# light_controller.net
KiCad netlist of a schematic drawn in EAGLE
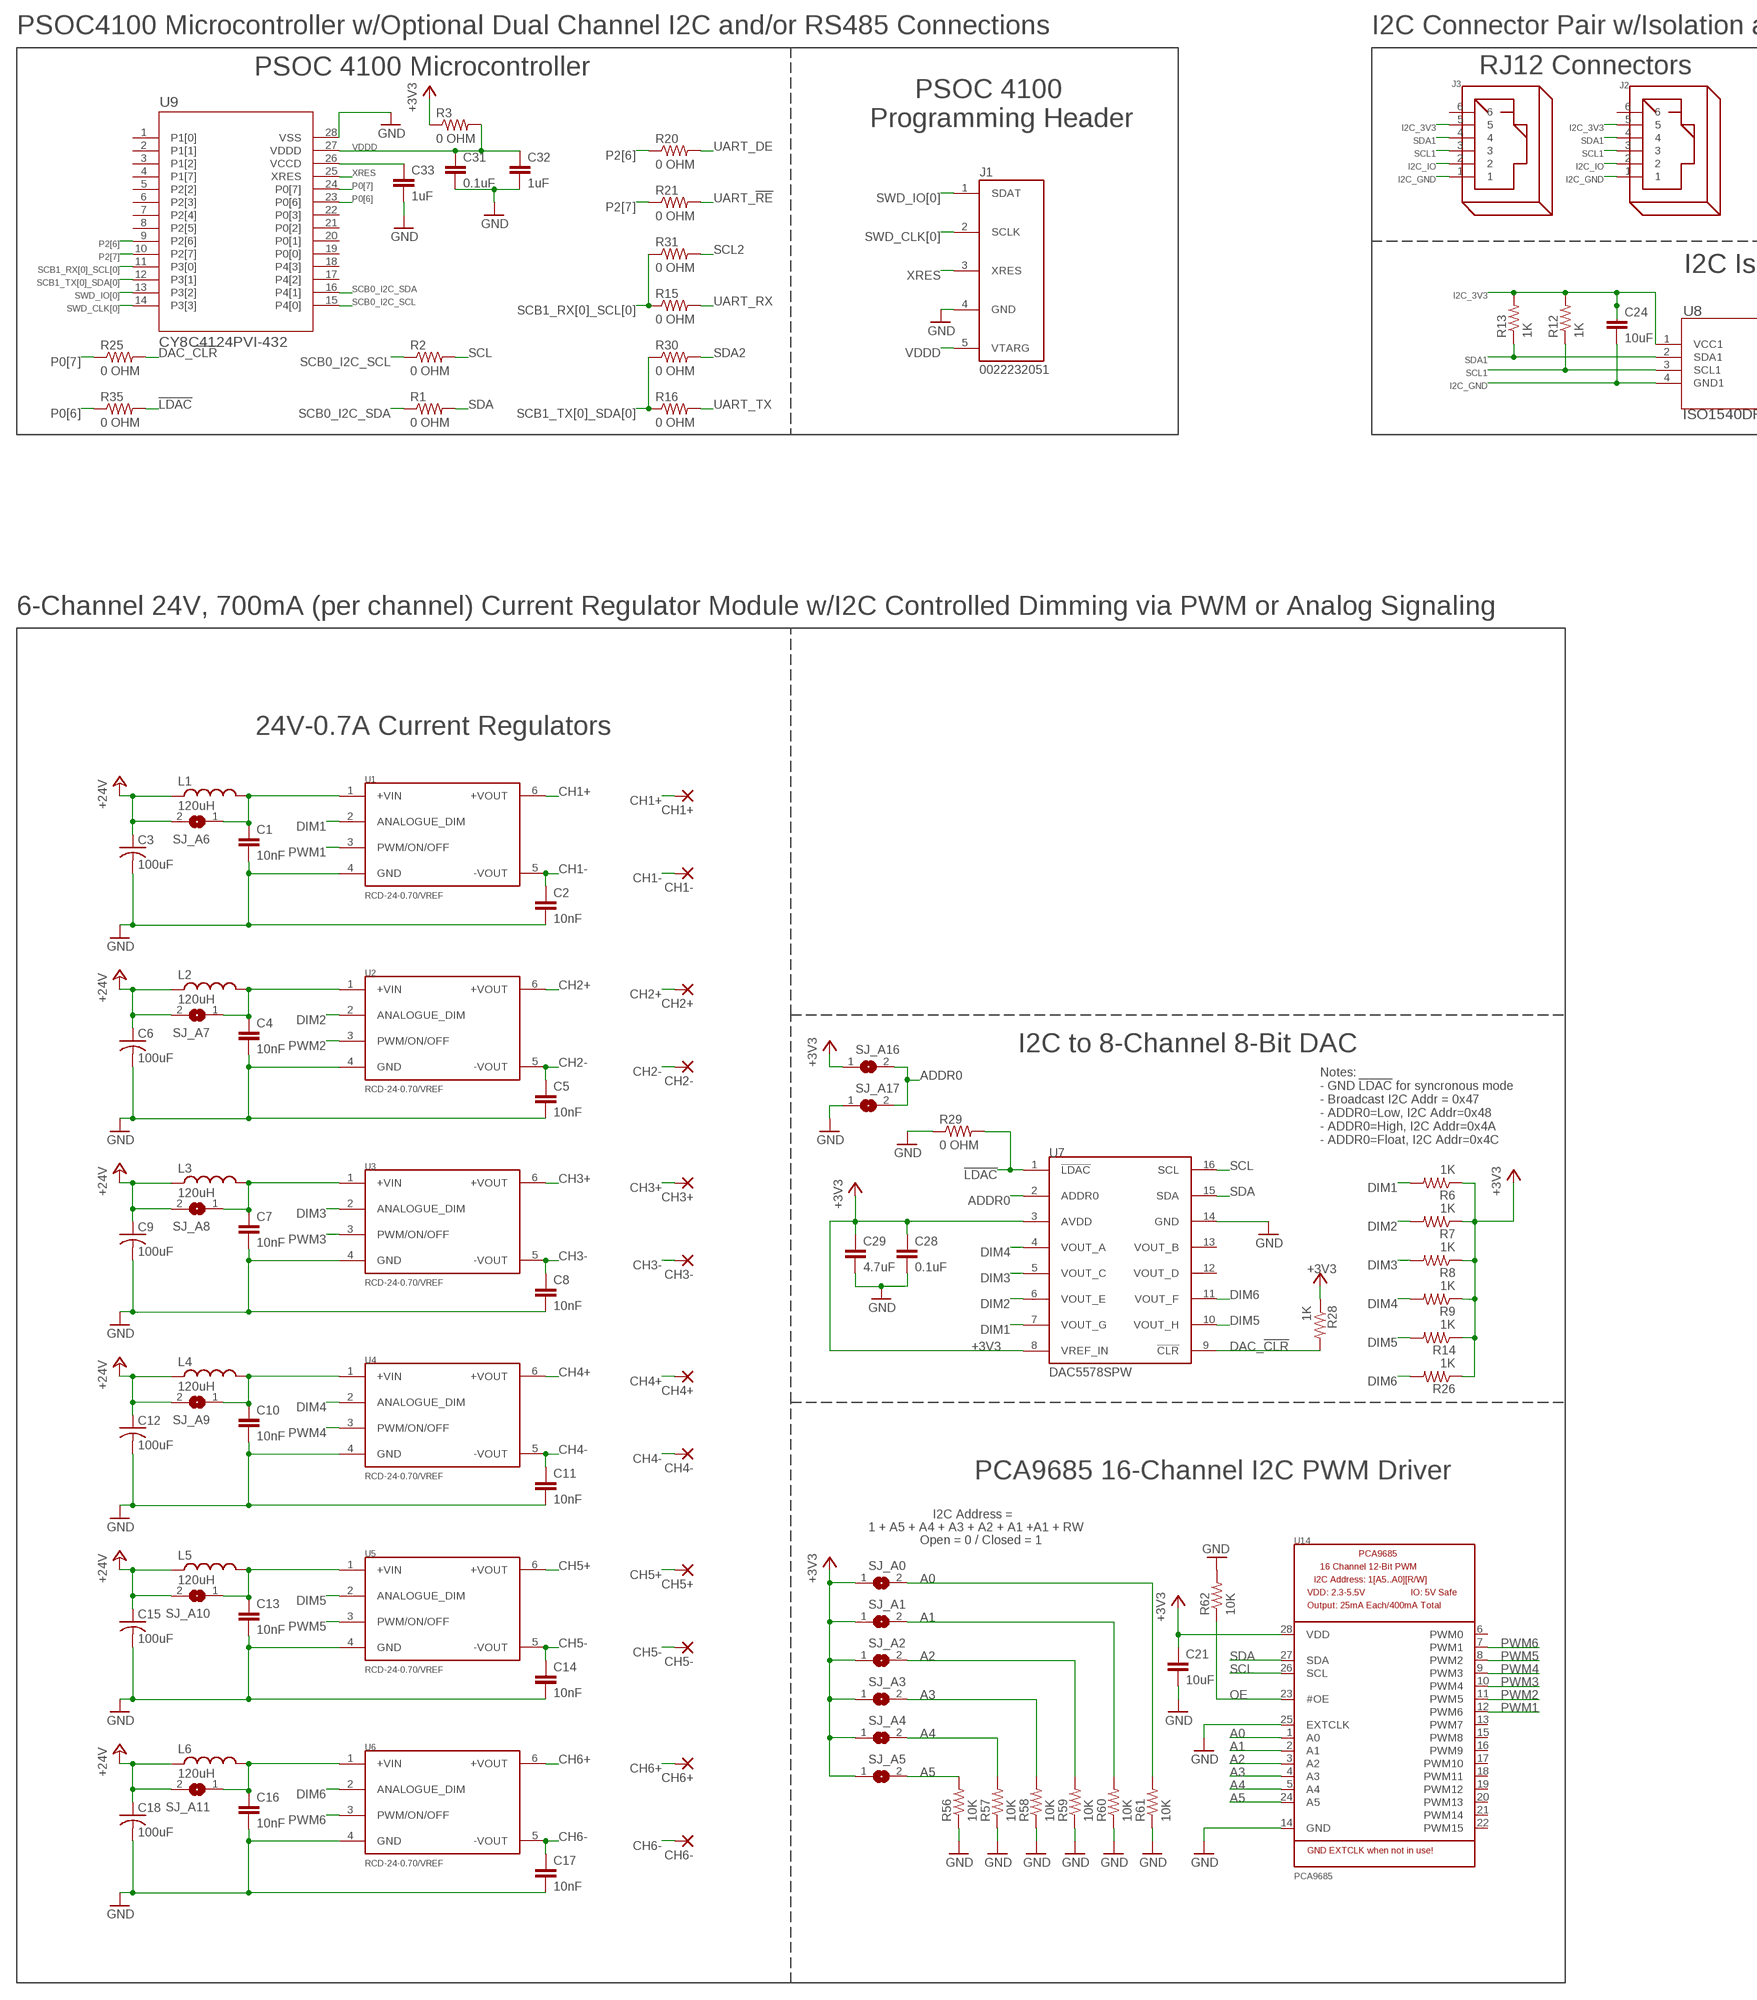
[diagram p0: schematic, sheet 1, part 1 of 2]
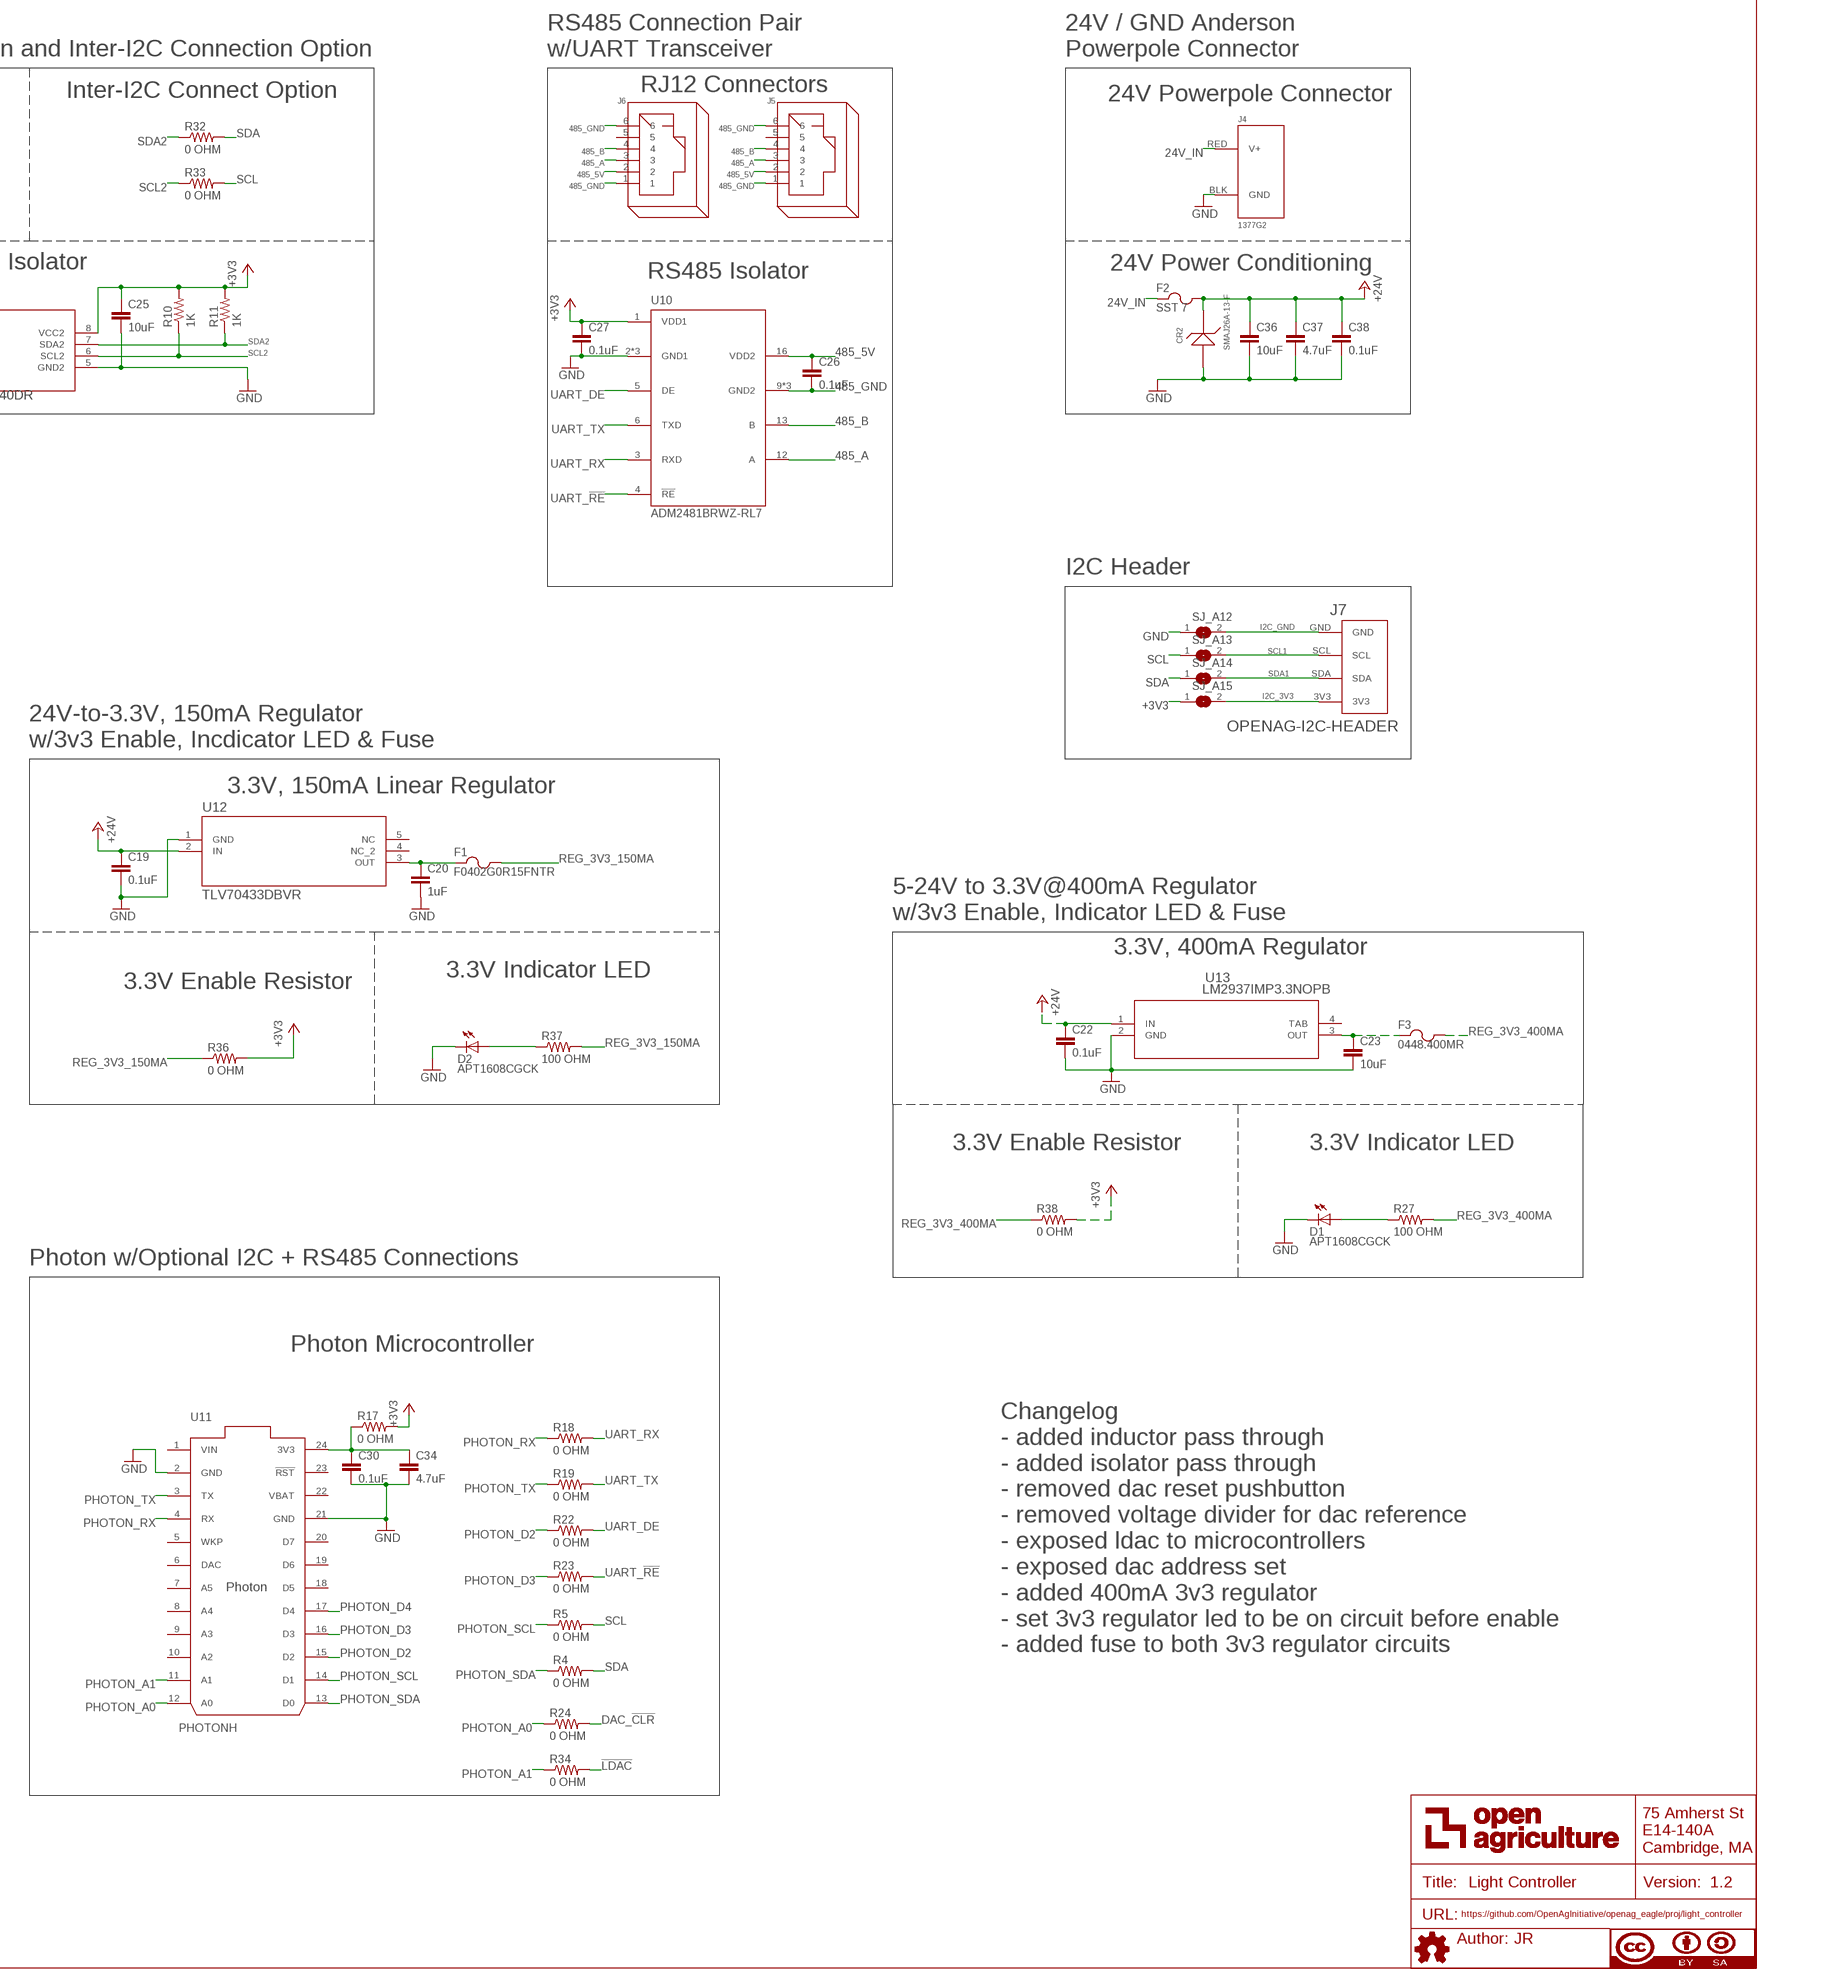
[diagram p1: schematic, sheet 1, part 2 of 2]

(export (version "E")
  (design (tool "Eeschema 10.0.6"))
  (components
    (comp (ref "C1")
      (value "10nF")
      (footprint "eagle-import:C0603")
      (libsource (lib "eagle-import") (part "10NF-C0603C103K5RACTU"))
    )
    (comp (ref "C2")
      (value "10nF")
      (footprint "eagle-import:C0603")
      (libsource (lib "eagle-import") (part "10NF-C0603C103K5RACTU"))
    )
    (comp (ref "C3")
      (value "100uF")
      (footprint "eagle-import:EEE-1HA101UP")
      (libsource (lib "eagle-import") (part "100UF-EEE-1HA101UP"))
    )
    (comp (ref "C4")
      (value "10nF")
      (footprint "eagle-import:C0603")
      (libsource (lib "eagle-import") (part "10NF-C0603C103K5RACTU"))
    )
    (comp (ref "C5")
      (value "10nF")
      (footprint "eagle-import:C0603")
      (libsource (lib "eagle-import") (part "10NF-C0603C103K5RACTU"))
    )
    (comp (ref "C6")
      (value "100uF")
      (footprint "eagle-import:EEE-1HA101UP")
      (libsource (lib "eagle-import") (part "100UF-EEE-1HA101UP"))
    )
    (comp (ref "C7")
      (value "10nF")
      (footprint "eagle-import:C0603")
      (libsource (lib "eagle-import") (part "10NF-C0603C103K5RACTU"))
    )
    (comp (ref "C8")
      (value "10nF")
      (footprint "eagle-import:C0603")
      (libsource (lib "eagle-import") (part "10NF-C0603C103K5RACTU"))
    )
    (comp (ref "C9")
      (value "100uF")
      (footprint "eagle-import:EEE-1HA101UP")
      (libsource (lib "eagle-import") (part "100UF-EEE-1HA101UP"))
    )
    (comp (ref "C10")
      (value "10nF")
      (footprint "eagle-import:C0603")
      (libsource (lib "eagle-import") (part "10NF-C0603C103K5RACTU"))
    )
    (comp (ref "C11")
      (value "10nF")
      (footprint "eagle-import:C0603")
      (libsource (lib "eagle-import") (part "10NF-C0603C103K5RACTU"))
    )
    (comp (ref "C12")
      (value "100uF")
      (footprint "eagle-import:EEE-1HA101UP")
      (libsource (lib "eagle-import") (part "100UF-EEE-1HA101UP"))
    )
    (comp (ref "C13")
      (value "10nF")
      (footprint "eagle-import:C0603")
      (libsource (lib "eagle-import") (part "10NF-C0603C103K5RACTU"))
    )
    (comp (ref "C14")
      (value "10nF")
      (footprint "eagle-import:C0603")
      (libsource (lib "eagle-import") (part "10NF-C0603C103K5RACTU"))
    )
    (comp (ref "C15")
      (value "100uF")
      (footprint "eagle-import:EEE-1HA101UP")
      (libsource (lib "eagle-import") (part "100UF-EEE-1HA101UP"))
    )
    (comp (ref "C16")
      (value "10nF")
      (footprint "eagle-import:C0603")
      (libsource (lib "eagle-import") (part "10NF-C0603C103K5RACTU"))
    )
    (comp (ref "C17")
      (value "10nF")
      (footprint "eagle-import:C0603")
      (libsource (lib "eagle-import") (part "10NF-C0603C103K5RACTU"))
    )
    (comp (ref "C18")
      (value "100uF")
      (footprint "eagle-import:EEE-1HA101UP")
      (libsource (lib "eagle-import") (part "100UF-EEE-1HA101UP"))
    )
    (comp (ref "C19")
      (value "0.1uF")
      (footprint "eagle-import:C0603")
      (libsource (lib "eagle-import") (part "0.1UF-C0603C104K5RACTU"))
    )
    (comp (ref "C20")
      (value "1uF")
      (footprint "eagle-import:C0603")
      (libsource (lib "eagle-import") (part "1UF-CL10A105KB8NNNC"))
    )
    (comp (ref "C21")
      (value "10uF")
      (footprint "eagle-import:C0805")
      (libsource (lib "eagle-import") (part "10UF-GMK212BBJ106KG-T"))
    )
    (comp (ref "C22")
      (value "0.1uF")
      (footprint "eagle-import:C0603")
      (libsource (lib "eagle-import") (part "0.1UF-C0603C104K5RACTU"))
    )
    (comp (ref "C23")
      (value "10uF")
      (footprint "eagle-import:C0805")
      (libsource (lib "eagle-import") (part "10UF-GMK212BBJ106KG-T"))
    )
    (comp (ref "C24")
      (value "10uF")
      (footprint "eagle-import:C0805")
      (libsource (lib "eagle-import") (part "10UF-GMK212BBJ106KG-T"))
    )
    (comp (ref "C25")
      (value "10uF")
      (footprint "eagle-import:C0805")
      (libsource (lib "eagle-import") (part "10UF-GMK212BBJ106KG-T"))
    )
    (comp (ref "C26")
      (value "0.1uF")
      (footprint "eagle-import:C0603")
      (libsource (lib "eagle-import") (part "0.1UF-C0603C104K5RACTU"))
    )
    (comp (ref "C27")
      (value "0.1uF")
      (footprint "eagle-import:C0603")
      (libsource (lib "eagle-import") (part "0.1UF-C0603C104K5RACTU"))
    )
    (comp (ref "C28")
      (value "0.1uF")
      (footprint "eagle-import:C0603")
      (libsource (lib "eagle-import") (part "0.1UF-C0603C104K5RACTU"))
    )
    (comp (ref "C29")
      (value "4.7uF")
      (footprint "eagle-import:C0805")
      (libsource (lib "eagle-import") (part "4.7UF-CL21A475KBQNNNE"))
    )
    (comp (ref "C30")
      (value "0.1uF")
      (footprint "eagle-import:C0603")
      (libsource (lib "eagle-import") (part "0.1UF-C0603C104K5RACTU"))
    )
    (comp (ref "C31")
      (value "0.1uF")
      (footprint "eagle-import:C0603")
      (libsource (lib "eagle-import") (part "0.1UF-C0603C104K5RACTU"))
    )
    (comp (ref "C32")
      (value "1uF")
      (footprint "eagle-import:C0603")
      (libsource (lib "eagle-import") (part "1UF-CL10A105KB8NNNC"))
    )
    (comp (ref "C33")
      (value "1uF")
      (footprint "eagle-import:C0603")
      (libsource (lib "eagle-import") (part "1UF-CL10A105KB8NNNC"))
    )
    (comp (ref "C34")
      (value "4.7uF")
      (footprint "eagle-import:C0805")
      (libsource (lib "eagle-import") (part "4.7UF-CL21A475KBQNNNE"))
    )
    (comp (ref "C36")
      (value "10uF")
      (footprint "eagle-import:C0805")
      (libsource (lib "eagle-import") (part "10UF-GMK212BBJ106KG-T"))
    )
    (comp (ref "C37")
      (value "4.7uF")
      (footprint "eagle-import:C0805")
      (libsource (lib "eagle-import") (part "4.7UF-CL21A475KBQNNNE"))
    )
    (comp (ref "C38")
      (value "0.1uF")
      (footprint "eagle-import:C0603")
      (libsource (lib "eagle-import") (part "0.1UF-C0603C104K5RACTU"))
    )
    (comp (ref "CH1+")
      (value "3,17/1,3")
      (footprint "eagle-import:3,17_1,3")
      (libsource (lib "eagle-import") (part "3,17/1,3"))
    )
    (comp (ref "CH1-")
      (value "3,17/1,3")
      (footprint "eagle-import:3,17_1,3")
      (libsource (lib "eagle-import") (part "3,17/1,3"))
    )
    (comp (ref "CH2+")
      (value "3,17/1,3")
      (footprint "eagle-import:3,17_1,3")
      (libsource (lib "eagle-import") (part "3,17/1,3"))
    )
    (comp (ref "CH2-")
      (value "3,17/1,3")
      (footprint "eagle-import:3,17_1,3")
      (libsource (lib "eagle-import") (part "3,17/1,3"))
    )
    (comp (ref "CH3+")
      (value "3,17/1,3")
      (footprint "eagle-import:3,17_1,3")
      (libsource (lib "eagle-import") (part "3,17/1,3"))
    )
    (comp (ref "CH3-")
      (value "3,17/1,3")
      (footprint "eagle-import:3,17_1,3")
      (libsource (lib "eagle-import") (part "3,17/1,3"))
    )
    (comp (ref "CH4+")
      (value "3,17/1,3")
      (footprint "eagle-import:3,17_1,3")
      (libsource (lib "eagle-import") (part "3,17/1,3"))
    )
    (comp (ref "CH4-")
      (value "3,17/1,3")
      (footprint "eagle-import:3,17_1,3")
      (libsource (lib "eagle-import") (part "3,17/1,3"))
    )
    (comp (ref "CH5+")
      (value "3,17/1,3")
      (footprint "eagle-import:3,17_1,3")
      (libsource (lib "eagle-import") (part "3,17/1,3"))
    )
    (comp (ref "CH5-")
      (value "3,17/1,3")
      (footprint "eagle-import:3,17_1,3")
      (libsource (lib "eagle-import") (part "3,17/1,3"))
    )
    (comp (ref "CH6+")
      (value "3,17/1,3")
      (footprint "eagle-import:3,17_1,3")
      (libsource (lib "eagle-import") (part "3,17/1,3"))
    )
    (comp (ref "CH6-")
      (value "3,17/1,3")
      (footprint "eagle-import:3,17_1,3")
      (libsource (lib "eagle-import") (part "3,17/1,3"))
    )
    (comp (ref "CR2")
      (value "SMAJ26A-13-F")
      (footprint "eagle-import:SMA")
      (libsource (lib "eagle-import") (part "SMAJ26A-13-F"))
    )
    (comp (ref "D1")
      (value "APT1608CGCK")
      (footprint "eagle-import:CHIPLED_0603")
      (libsource (lib "eagle-import") (part "APT1608CGCK"))
    )
    (comp (ref "D2")
      (value "APT1608CGCK")
      (footprint "eagle-import:CHIPLED_0603")
      (libsource (lib "eagle-import") (part "APT1608CGCK"))
    )
    (comp (ref "F1")
      (value "F0402G0R15FNTR")
      (footprint "eagle-import:0402")
      (libsource (lib "eagle-import") (part "F0402G0R15FNTR"))
    )
    (comp (ref "F2")
      (value "SST 7")
      (footprint "eagle-import:SS")
      (libsource (lib "eagle-import") (part "SST_7"))
    )
    (comp (ref "F3")
      (value "0448.400MR")
      (footprint "eagle-import:0603")
      (libsource (lib "eagle-import") (part "0438.375WR"))
    )
    (comp (ref "FRAME1")
      (value "DOCFIELD")
      (footprint "eagle-import:DOCFIELD")
      (description "Controls 6 channels of 24V, 700mA for LED strings that can be interfaced via i2c, rs485, and/or wifi.")
      (fields
        (field (name "TITLE") "Example Template")
        (field (name "AUTHOR") "XX")
        (field (name "VER") "1.0")
        (field (name "URL") "https://github.com/OpenAgInitiative/openag_eagle_template")
        (field (name "AUTHOR_1") "JR")
        (field (name "TITLE_1") "Light Controller")
        (field (name "URL_1") "https://github.com/OpenAgInitiative/openag_eagle/proj/light_controller")
        (field (name "VER_1") "1.2")
      )
      (libsource (lib "eagle-import") (part "DOCFIELD"))
    )
    (comp (ref "J1")
      (value "0022232051")
      (footprint "eagle-import:22-23-2051")
      (libsource (lib "eagle-import") (part "MINI-PROG3-5POS-MATING-CONNECTOR"))
    )
    (comp (ref "J2")
      (value "OPENAG-I2C-RJ12")
      (footprint "eagle-import:OPENAG-I2C-RJ12")
      (fields (field (name "MPN") "A-2004-1-4-LP-N-R"))
      (libsource (lib "eagle-import") (part "OPENAG-I2C-RJ12"))
    )
    (comp (ref "J3")
      (value "OPENAG-I2C-RJ12")
      (footprint "eagle-import:OPENAG-I2C-RJ12")
      (fields (field (name "MPN") "A-2004-1-4-LP-N-R"))
      (libsource (lib "eagle-import") (part "OPENAG-I2C-RJ12"))
    )
    (comp (ref "J4")
      (value "1377G2")
      (footprint "eagle-import:1377G2")
      (libsource (lib "eagle-import") (part "1377G21377G2"))
    )
    (comp (ref "J5")
      (value "OPENAG-RS485-RJ12")
      (footprint "eagle-import:OPENAG-RS485-RJ12")
      (libsource (lib "eagle-import") (part "OPENAG-RS485-RJ12"))
    )
    (comp (ref "J6")
      (value "OPENAG-RS485-RJ12")
      (footprint "eagle-import:OPENAG-RS485-RJ12")
      (libsource (lib "eagle-import") (part "OPENAG-RS485-RJ12"))
    )
    (comp (ref "J7")
      (value "OPENAG-I2C-HEADER")
      (footprint "eagle-import:OPENAG-I2C-HEADER")
      (libsource (lib "eagle-import") (part "OPENAG-I2C-HEADER"))
    )
    (comp (ref "L1")
      (value "120uH")
      (footprint "eagle-import:74404064121")
      (libsource (lib "eagle-import") (part "120UH-74404064121"))
    )
    (comp (ref "L2")
      (value "120uH")
      (footprint "eagle-import:74404064121")
      (libsource (lib "eagle-import") (part "120UH-74404064121"))
    )
    (comp (ref "L3")
      (value "120uH")
      (footprint "eagle-import:74404064121")
      (libsource (lib "eagle-import") (part "120UH-74404064121"))
    )
    (comp (ref "L4")
      (value "120uH")
      (footprint "eagle-import:74404064121")
      (libsource (lib "eagle-import") (part "120UH-74404064121"))
    )
    (comp (ref "L5")
      (value "120uH")
      (footprint "eagle-import:74404064121")
      (libsource (lib "eagle-import") (part "120UH-74404064121"))
    )
    (comp (ref "L6")
      (value "120uH")
      (footprint "eagle-import:74404064121")
      (libsource (lib "eagle-import") (part "120UH-74404064121"))
    )
    (comp (ref "R1")
      (value "0 OHM")
      (footprint "eagle-import:RC0603N")
      (libsource (lib "eagle-import") (part "0OHM-RC0603JR-070RL"))
    )
    (comp (ref "R2")
      (value "0 OHM")
      (footprint "eagle-import:RC0603N")
      (libsource (lib "eagle-import") (part "0OHM-RC0603JR-070RL"))
    )
    (comp (ref "R3")
      (value "0 OHM")
      (footprint "eagle-import:RC0603N")
      (libsource (lib "eagle-import") (part "0OHM-RC0603JR-070RL"))
    )
    (comp (ref "R4")
      (value "0 OHM")
      (footprint "eagle-import:RC0603N")
      (libsource (lib "eagle-import") (part "0OHM-RC0603JR-070RL"))
    )
    (comp (ref "R5")
      (value "0 OHM")
      (footprint "eagle-import:RC0603N")
      (libsource (lib "eagle-import") (part "0OHM-RC0603JR-070RL"))
    )
    (comp (ref "R6")
      (value "1K")
      (footprint "eagle-import:RC0603N")
      (libsource (lib "eagle-import") (part "1K-ERJ-PB3D1001V"))
    )
    (comp (ref "R7")
      (value "1K")
      (footprint "eagle-import:RC0603N")
      (libsource (lib "eagle-import") (part "1K-ERJ-PB3D1001V"))
    )
    (comp (ref "R8")
      (value "1K")
      (footprint "eagle-import:RC0603N")
      (libsource (lib "eagle-import") (part "1K-ERJ-PB3D1001V"))
    )
    (comp (ref "R9")
      (value "1K")
      (footprint "eagle-import:RC0603N")
      (libsource (lib "eagle-import") (part "1K-ERJ-PB3D1001V"))
    )
    (comp (ref "R10")
      (value "1K")
      (footprint "eagle-import:RC0603N")
      (libsource (lib "eagle-import") (part "1K-ERJ-PB3D1001V"))
    )
    (comp (ref "R11")
      (value "1K")
      (footprint "eagle-import:RC0603N")
      (libsource (lib "eagle-import") (part "1K-ERJ-PB3D1001V"))
    )
    (comp (ref "R12")
      (value "1K")
      (footprint "eagle-import:RC0603N")
      (libsource (lib "eagle-import") (part "1K-ERJ-PB3D1001V"))
    )
    (comp (ref "R13")
      (value "1K")
      (footprint "eagle-import:RC0603N")
      (libsource (lib "eagle-import") (part "1K-ERJ-PB3D1001V"))
    )
    (comp (ref "R14")
      (value "1K")
      (footprint "eagle-import:RC0603N")
      (libsource (lib "eagle-import") (part "1K-ERJ-PB3D1001V"))
    )
    (comp (ref "R15")
      (value "0 OHM")
      (footprint "eagle-import:RC0603N")
      (libsource (lib "eagle-import") (part "0OHM-RC0603JR-070RL"))
    )
    (comp (ref "R16")
      (value "0 OHM")
      (footprint "eagle-import:RC0603N")
      (libsource (lib "eagle-import") (part "0OHM-RC0603JR-070RL"))
    )
    (comp (ref "R17")
      (value "0 OHM")
      (footprint "eagle-import:RC0603N")
      (libsource (lib "eagle-import") (part "0OHM-RC0603JR-070RL"))
    )
    (comp (ref "R18")
      (value "0 OHM")
      (footprint "eagle-import:RC0603N")
      (libsource (lib "eagle-import") (part "0OHM-RC0603JR-070RL"))
    )
    (comp (ref "R19")
      (value "0 OHM")
      (footprint "eagle-import:RC0603N")
      (libsource (lib "eagle-import") (part "0OHM-RC0603JR-070RL"))
    )
    (comp (ref "R20")
      (value "0 OHM")
      (footprint "eagle-import:RC0603N")
      (libsource (lib "eagle-import") (part "0OHM-RC0603JR-070RL"))
    )
    (comp (ref "R21")
      (value "0 OHM")
      (footprint "eagle-import:RC0603N")
      (libsource (lib "eagle-import") (part "0OHM-RC0603JR-070RL"))
    )
    (comp (ref "R22")
      (value "0 OHM")
      (footprint "eagle-import:RC0603N")
      (libsource (lib "eagle-import") (part "0OHM-RC0603JR-070RL"))
    )
    (comp (ref "R23")
      (value "0 OHM")
      (footprint "eagle-import:RC0603N")
      (libsource (lib "eagle-import") (part "0OHM-RC0603JR-070RL"))
    )
    (comp (ref "R24")
      (value "0 OHM")
      (footprint "eagle-import:RC0603N")
      (libsource (lib "eagle-import") (part "0OHM-RC0603JR-070RL"))
    )
    (comp (ref "R25")
      (value "0 OHM")
      (footprint "eagle-import:RC0603N")
      (libsource (lib "eagle-import") (part "0OHM-RC0603JR-070RL"))
    )
    (comp (ref "R26")
      (value "1K")
      (footprint "eagle-import:RC0603N")
      (libsource (lib "eagle-import") (part "1K-ERJ-PB3D1001V"))
    )
    (comp (ref "R27")
      (value "100 OHM")
      (footprint "eagle-import:RC0603N")
      (libsource (lib "eagle-import") (part "100OHM-RC0603JR-07100RL"))
    )
    (comp (ref "R28")
      (value "1K")
      (footprint "eagle-import:RC0603N")
      (libsource (lib "eagle-import") (part "1K-ERJ-PB3D1001V"))
    )
    (comp (ref "R29")
      (value "0 OHM")
      (footprint "eagle-import:RC0603N")
      (libsource (lib "eagle-import") (part "0OHM-RC0603JR-070RL"))
    )
    (comp (ref "R30")
      (value "0 OHM")
      (footprint "eagle-import:RC0603N")
      (libsource (lib "eagle-import") (part "0OHM-RC0603JR-070RL"))
    )
    (comp (ref "R31")
      (value "0 OHM")
      (footprint "eagle-import:RC0603N")
      (libsource (lib "eagle-import") (part "0OHM-RC0603JR-070RL"))
    )
    (comp (ref "R32")
      (value "0 OHM")
      (footprint "eagle-import:RC0603N")
      (libsource (lib "eagle-import") (part "0OHM-RC0603JR-070RL"))
    )
    (comp (ref "R33")
      (value "0 OHM")
      (footprint "eagle-import:RC0603N")
      (libsource (lib "eagle-import") (part "0OHM-RC0603JR-070RL"))
    )
    (comp (ref "R34")
      (value "0 OHM")
      (footprint "eagle-import:RC0603N")
      (libsource (lib "eagle-import") (part "0OHM-RC0603JR-070RL"))
    )
    (comp (ref "R35")
      (value "0 OHM")
      (footprint "eagle-import:RC0603N")
      (libsource (lib "eagle-import") (part "0OHM-RC0603JR-070RL"))
    )
    (comp (ref "R36")
      (value "0 OHM")
      (footprint "eagle-import:RC0603N")
      (libsource (lib "eagle-import") (part "0OHM-RC0603JR-070RL"))
    )
    (comp (ref "R37")
      (value "100 OHM")
      (footprint "eagle-import:RC0603N")
      (libsource (lib "eagle-import") (part "100OHM-RC0603JR-07100RL"))
    )
    (comp (ref "R38")
      (value "0 OHM")
      (footprint "eagle-import:RC0603N")
      (libsource (lib "eagle-import") (part "0OHM-RC0603JR-070RL"))
    )
    (comp (ref "R56")
      (value "10K")
      (footprint "eagle-import:RC0603N")
      (libsource (lib "eagle-import") (part "10K-ERJ-3EKF1002V"))
    )
    (comp (ref "R57")
      (value "10K")
      (footprint "eagle-import:RC0603N")
      (libsource (lib "eagle-import") (part "10K-ERJ-3EKF1002V"))
    )
    (comp (ref "R58")
      (value "10K")
      (footprint "eagle-import:RC0603N")
      (libsource (lib "eagle-import") (part "10K-ERJ-3EKF1002V"))
    )
    (comp (ref "R59")
      (value "10K")
      (footprint "eagle-import:RC0603N")
      (libsource (lib "eagle-import") (part "10K-ERJ-3EKF1002V"))
    )
    (comp (ref "R60")
      (value "10K")
      (footprint "eagle-import:RC0603N")
      (libsource (lib "eagle-import") (part "10K-ERJ-3EKF1002V"))
    )
    (comp (ref "R61")
      (value "10K")
      (footprint "eagle-import:RC0603N")
      (libsource (lib "eagle-import") (part "10K-ERJ-3EKF1002V"))
    )
    (comp (ref "R62")
      (value "10K")
      (footprint "eagle-import:RC0603N")
      (libsource (lib "eagle-import") (part "10K-ERJ-3EKF1002V"))
    )
    (comp (ref "SJ_A0")
      (value "SOLDERJUMPERREFLOW_NOPASTE")
      (footprint "eagle-import:SOLDERJUMPER_REFLOW_NOPASTE")
      (libsource (lib "eagle-import") (part "SOLDERJUMPERREFLOW_NOPASTE"))
    )
    (comp (ref "SJ_A1")
      (value "SOLDERJUMPERREFLOW_NOPASTE")
      (footprint "eagle-import:SOLDERJUMPER_REFLOW_NOPASTE")
      (libsource (lib "eagle-import") (part "SOLDERJUMPERREFLOW_NOPASTE"))
    )
    (comp (ref "SJ_A2")
      (value "SOLDERJUMPERREFLOW_NOPASTE")
      (footprint "eagle-import:SOLDERJUMPER_REFLOW_NOPASTE")
      (libsource (lib "eagle-import") (part "SOLDERJUMPERREFLOW_NOPASTE"))
    )
    (comp (ref "SJ_A3")
      (value "SOLDERJUMPERREFLOW_NOPASTE")
      (footprint "eagle-import:SOLDERJUMPER_REFLOW_NOPASTE")
      (libsource (lib "eagle-import") (part "SOLDERJUMPERREFLOW_NOPASTE"))
    )
    (comp (ref "SJ_A4")
      (value "SOLDERJUMPERREFLOW_NOPASTE")
      (footprint "eagle-import:SOLDERJUMPER_REFLOW_NOPASTE")
      (libsource (lib "eagle-import") (part "SOLDERJUMPERREFLOW_NOPASTE"))
    )
    (comp (ref "SJ_A5")
      (value "SOLDERJUMPERREFLOW_NOPASTE")
      (footprint "eagle-import:SOLDERJUMPER_REFLOW_NOPASTE")
      (libsource (lib "eagle-import") (part "SOLDERJUMPERREFLOW_NOPASTE"))
    )
    (comp (ref "SJ_A6")
      (value "SOLDERJUMPERREFLOW_NOPASTE")
      (footprint "eagle-import:SOLDERJUMPER_REFLOW_NOPASTE")
      (libsource (lib "eagle-import") (part "SOLDERJUMPERREFLOW_NOPASTE"))
    )
    (comp (ref "SJ_A7")
      (value "SOLDERJUMPERREFLOW_NOPASTE")
      (footprint "eagle-import:SOLDERJUMPER_REFLOW_NOPASTE")
      (libsource (lib "eagle-import") (part "SOLDERJUMPERREFLOW_NOPASTE"))
    )
    (comp (ref "SJ_A8")
      (value "SOLDERJUMPERREFLOW_NOPASTE")
      (footprint "eagle-import:SOLDERJUMPER_REFLOW_NOPASTE")
      (libsource (lib "eagle-import") (part "SOLDERJUMPERREFLOW_NOPASTE"))
    )
    (comp (ref "SJ_A9")
      (value "SOLDERJUMPERREFLOW_NOPASTE")
      (footprint "eagle-import:SOLDERJUMPER_REFLOW_NOPASTE")
      (libsource (lib "eagle-import") (part "SOLDERJUMPERREFLOW_NOPASTE"))
    )
    (comp (ref "SJ_A10")
      (value "SOLDERJUMPERREFLOW_NOPASTE")
      (footprint "eagle-import:SOLDERJUMPER_REFLOW_NOPASTE")
      (libsource (lib "eagle-import") (part "SOLDERJUMPERREFLOW_NOPASTE"))
    )
    (comp (ref "SJ_A11")
      (value "SOLDERJUMPERREFLOW_NOPASTE")
      (footprint "eagle-import:SOLDERJUMPER_REFLOW_NOPASTE")
      (libsource (lib "eagle-import") (part "SOLDERJUMPERREFLOW_NOPASTE"))
    )
    (comp (ref "SJ_A12")
      (value "SOLDERJUMPERREFLOW_NOPASTE")
      (footprint "eagle-import:SOLDERJUMPER_REFLOW_NOPASTE")
      (libsource (lib "eagle-import") (part "SOLDERJUMPERREFLOW_NOPASTE"))
    )
    (comp (ref "SJ_A13")
      (value "SOLDERJUMPERREFLOW_NOPASTE")
      (footprint "eagle-import:SOLDERJUMPER_REFLOW_NOPASTE")
      (libsource (lib "eagle-import") (part "SOLDERJUMPERREFLOW_NOPASTE"))
    )
    (comp (ref "SJ_A14")
      (value "SOLDERJUMPERREFLOW_NOPASTE")
      (footprint "eagle-import:SOLDERJUMPER_REFLOW_NOPASTE")
      (libsource (lib "eagle-import") (part "SOLDERJUMPERREFLOW_NOPASTE"))
    )
    (comp (ref "SJ_A15")
      (value "SOLDERJUMPERREFLOW_NOPASTE")
      (footprint "eagle-import:SOLDERJUMPER_REFLOW_NOPASTE")
      (libsource (lib "eagle-import") (part "SOLDERJUMPERREFLOW_NOPASTE"))
    )
    (comp (ref "SJ_A16")
      (value "SOLDERJUMPERREFLOW_NOPASTE")
      (footprint "eagle-import:SOLDERJUMPER_REFLOW_NOPASTE")
      (libsource (lib "eagle-import") (part "SOLDERJUMPERREFLOW_NOPASTE"))
    )
    (comp (ref "SJ_A17")
      (value "SOLDERJUMPERREFLOW_NOPASTE")
      (footprint "eagle-import:SOLDERJUMPER_REFLOW_NOPASTE")
      (libsource (lib "eagle-import") (part "SOLDERJUMPERREFLOW_NOPASTE"))
    )
    (comp (ref "U1")
      (value "RCD-24-0.70/VREF")
      (footprint "eagle-import:RCD-24-PINNED")
      (libsource (lib "eagle-import") (part "RCD-24-0.70/VREF"))
    )
    (comp (ref "U2")
      (value "RCD-24-0.70/VREF")
      (footprint "eagle-import:RCD-24-PINNED")
      (libsource (lib "eagle-import") (part "RCD-24-0.70/VREF"))
    )
    (comp (ref "U3")
      (value "RCD-24-0.70/VREF")
      (footprint "eagle-import:RCD-24-PINNED")
      (libsource (lib "eagle-import") (part "RCD-24-0.70/VREF"))
    )
    (comp (ref "U4")
      (value "RCD-24-0.70/VREF")
      (footprint "eagle-import:RCD-24-PINNED")
      (libsource (lib "eagle-import") (part "RCD-24-0.70/VREF"))
    )
    (comp (ref "U5")
      (value "RCD-24-0.70/VREF")
      (footprint "eagle-import:RCD-24-PINNED")
      (libsource (lib "eagle-import") (part "RCD-24-0.70/VREF"))
    )
    (comp (ref "U6")
      (value "RCD-24-0.70/VREF")
      (footprint "eagle-import:RCD-24-PINNED")
      (libsource (lib "eagle-import") (part "RCD-24-0.70/VREF"))
    )
    (comp (ref "U7")
      (value "DAC5578SPW")
      (footprint "eagle-import:TSSOP16")
      (libsource (lib "eagle-import") (part "DAC5578SPW"))
    )
    (comp (ref "U8")
      (value "ISO1540DR")
      (footprint "eagle-import:D8")
      (libsource (lib "eagle-import") (part "ISO1540DR"))
    )
    (comp (ref "U9")
      (value "CY8C4124PVI-432")
      (footprint "eagle-import:SSOP-28")
      (libsource (lib "eagle-import") (part "CY8C4124PVI-432"))
    )
    (comp (ref "U10")
      (value "ADM2481BRWZ-RL7")
      (footprint "eagle-import:SOIC16LWB")
      (libsource (lib "eagle-import") (part "ADM2481BRWZ-RL7"))
    )
    (comp (ref "U11")
      (value "PHOTONH")
      (footprint "eagle-import:PHOTON")
      (libsource (lib "eagle-import") (part "PHOTONHPHOTONH"))
    )
    (comp (ref "U12")
      (value "TLV70433DBVR")
      (footprint "eagle-import:DBV5-M")
      (libsource (lib "eagle-import") (part "TLV70433DBVRDBV5-M"))
    )
    (comp (ref "U13")
      (value "LM2937IMP3.3NOPB")
      (footprint "eagle-import:MP04A")
      (libsource (lib "eagle-import") (part "LM2937IMP-3.3/NOPB"))
    )
    (comp (ref "U14")
      (value "PCA9685")
      (footprint "eagle-import:TSSOP28")
      (libsource (lib "eagle-import") (part "PCA9685PW/Q900,118"))
    )
  )
  (nets
    (net (code "1") (name "+3V3") (class "Default")
      (node (ref "C21") (pin "1") (pinfunction "1_1") (pintype "passive"))
      (node (ref "C25") (pin "1") (pinfunction "1_1") (pintype "passive"))
      (node (ref "C27") (pin "1") (pinfunction "1_1") (pintype "passive"))
      (node (ref "C28") (pin "1") (pinfunction "1_1") (pintype "passive"))
      (node (ref "C29") (pin "1") (pinfunction "1_1") (pintype "passive"))
      (node (ref "R10") (pin "2") (pinfunction "2_2") (pintype "passive"))
      (node (ref "R11") (pin "2") (pinfunction "2_2") (pintype "passive"))
      (node (ref "R14") (pin "1") (pinfunction "1_1") (pintype "passive"))
      (node (ref "R17") (pin "2") (pinfunction "2_2") (pintype "passive"))
      (node (ref "R26") (pin "1") (pinfunction "1_1") (pintype "passive"))
      (node (ref "R28") (pin "1") (pinfunction "1_1") (pintype "passive"))
      (node (ref "R3") (pin "1") (pinfunction "1_1") (pintype "passive"))
      (node (ref "R36") (pin "2") (pinfunction "2_2") (pintype "passive"))
      (node (ref "R38") (pin "2") (pinfunction "2_2") (pintype "passive"))
      (node (ref "R6") (pin "1") (pinfunction "1_1") (pintype "passive"))
      (node (ref "R7") (pin "1") (pinfunction "1_1") (pintype "passive"))
      (node (ref "R8") (pin "1") (pinfunction "1_1") (pintype "passive"))
      (node (ref "R9") (pin "1") (pinfunction "1_1") (pintype "passive"))
      (node (ref "SJ_A0") (pin "1") (pinfunction "1_1") (pintype "passive"))
      (node (ref "SJ_A1") (pin "1") (pinfunction "1_1") (pintype "passive"))
      (node (ref "SJ_A15") (pin "1") (pinfunction "1_1") (pintype "passive"))
      (node (ref "SJ_A16") (pin "1") (pinfunction "1_1") (pintype "passive"))
      (node (ref "SJ_A2") (pin "1") (pinfunction "1_1") (pintype "passive"))
      (node (ref "SJ_A3") (pin "1") (pinfunction "1_1") (pintype "passive"))
      (node (ref "SJ_A4") (pin "1") (pinfunction "1_1") (pintype "passive"))
      (node (ref "SJ_A5") (pin "1") (pinfunction "1_1") (pintype "passive"))
      (node (ref "U10") (pin "1") (pinfunction "VDD1_1") (pintype "bidirectional"))
      (node (ref "U14") (pin "28") (pinfunction "VDD_28") (pintype "power_in"))
      (node (ref "U7") (pin "3") (pinfunction "AVDD_3") (pintype "bidirectional"))
      (node (ref "U7") (pin "8") (pinfunction "VREF_IN_8") (pintype "bidirectional"))
      (node (ref "U8") (pin "8") (pinfunction "VCC2_8") (pintype "power_in"))
    )
    (net (code "2") (name "+24V") (class "Default")
      (node (ref "C12") (pin "+") (pinfunction "1(+)_+") (pintype "passive"))
      (node (ref "C15") (pin "+") (pinfunction "1(+)_+") (pintype "passive"))
      (node (ref "C18") (pin "+") (pinfunction "1(+)_+") (pintype "passive"))
      (node (ref "C19") (pin "1") (pinfunction "1_1") (pintype "passive"))
      (node (ref "C22") (pin "1") (pinfunction "1_1") (pintype "passive"))
      (node (ref "C3") (pin "+") (pinfunction "1(+)_+") (pintype "passive"))
      (node (ref "C36") (pin "1") (pinfunction "1_1") (pintype "passive"))
      (node (ref "C37") (pin "1") (pinfunction "1_1") (pintype "passive"))
      (node (ref "C38") (pin "1") (pinfunction "1_1") (pintype "passive"))
      (node (ref "C6") (pin "+") (pinfunction "1(+)_+") (pintype "passive"))
      (node (ref "C9") (pin "+") (pinfunction "1(+)_+") (pintype "passive"))
      (node (ref "CR2") (pin "1") (pinfunction "P$2_1") (pintype "bidirectional"))
      (node (ref "F2") (pin "2") (pinfunction "2_2") (pintype "passive"))
      (node (ref "L1") (pin "1") (pinfunction "1_1") (pintype "passive"))
      (node (ref "L2") (pin "1") (pinfunction "1_1") (pintype "passive"))
      (node (ref "L3") (pin "1") (pinfunction "1_1") (pintype "passive"))
      (node (ref "L4") (pin "1") (pinfunction "1_1") (pintype "passive"))
      (node (ref "L5") (pin "1") (pinfunction "1_1") (pintype "passive"))
      (node (ref "L6") (pin "1") (pinfunction "1_1") (pintype "passive"))
      (node (ref "SJ_A10") (pin "2") (pinfunction "2_2") (pintype "passive"))
      (node (ref "SJ_A11") (pin "2") (pinfunction "2_2") (pintype "passive"))
      (node (ref "SJ_A6") (pin "2") (pinfunction "2_2") (pintype "passive"))
      (node (ref "SJ_A7") (pin "2") (pinfunction "2_2") (pintype "passive"))
      (node (ref "SJ_A8") (pin "2") (pinfunction "2_2") (pintype "passive"))
      (node (ref "SJ_A9") (pin "2") (pinfunction "2_2") (pintype "passive"))
      (node (ref "U12") (pin "2") (pinfunction "IN_2") (pintype "input"))
      (node (ref "U13") (pin "1") (pinfunction "IN_1") (pintype "power_in"))
    )
    (net (code "3") (name "/A0") (class "Default")
      (node (ref "R61") (pin "2") (pinfunction "2_2") (pintype "passive"))
      (node (ref "SJ_A0") (pin "2") (pinfunction "2_2") (pintype "passive"))
      (node (ref "U14") (pin "1") (pinfunction "A0_1") (pintype "bidirectional"))
    )
    (net (code "4") (name "/A1") (class "Default")
      (node (ref "R60") (pin "2") (pinfunction "2_2") (pintype "passive"))
      (node (ref "SJ_A1") (pin "2") (pinfunction "2_2") (pintype "passive"))
      (node (ref "U14") (pin "2") (pinfunction "A1_2") (pintype "bidirectional"))
    )
    (net (code "5") (name "/A2") (class "Default")
      (node (ref "R59") (pin "2") (pinfunction "2_2") (pintype "passive"))
      (node (ref "SJ_A2") (pin "2") (pinfunction "2_2") (pintype "passive"))
      (node (ref "U14") (pin "3") (pinfunction "A2_3") (pintype "bidirectional"))
    )
    (net (code "6") (name "/A3") (class "Default")
      (node (ref "R58") (pin "2") (pinfunction "2_2") (pintype "passive"))
      (node (ref "SJ_A3") (pin "2") (pinfunction "2_2") (pintype "passive"))
      (node (ref "U14") (pin "4") (pinfunction "A3_4") (pintype "bidirectional"))
    )
    (net (code "7") (name "/A4") (class "Default")
      (node (ref "R57") (pin "2") (pinfunction "2_2") (pintype "passive"))
      (node (ref "SJ_A4") (pin "2") (pinfunction "2_2") (pintype "passive"))
      (node (ref "U14") (pin "5") (pinfunction "A4_5") (pintype "bidirectional"))
    )
    (net (code "8") (name "/A5") (class "Default")
      (node (ref "R56") (pin "2") (pinfunction "2_2") (pintype "passive"))
      (node (ref "SJ_A5") (pin "2") (pinfunction "2_2") (pintype "passive"))
      (node (ref "U14") (pin "24") (pinfunction "A5_24") (pintype "bidirectional"))
    )
    (net (code "9") (name "/DAC_~{CLR}") (class "Default")
      (node (ref "R24") (pin "2") (pinfunction "2_2") (pintype "passive"))
      (node (ref "R25") (pin "2") (pinfunction "2_2") (pintype "passive"))
      (node (ref "R28") (pin "2") (pinfunction "2_2") (pintype "passive"))
      (node (ref "U7") (pin "9") (pinfunction "~{CLR}_9") (pintype "bidirectional"))
    )
    (net (code "10") (name "/OE") (class "Default")
      (node (ref "R62") (pin "1") (pinfunction "1_1") (pintype "passive"))
      (node (ref "U14") (pin "23") (pinfunction "#OE_23") (pintype "input"))
    )
    (net (code "11") (name "/TAB") (class "Default")
      (node (ref "U13") (pin "4") (pinfunction "TAB_4") (pintype "power_in"))
    )
    (net (code "12") (name "/UART_~{RE}") (class "Default")
      (node (ref "R21") (pin "2") (pinfunction "2_2") (pintype "passive"))
      (node (ref "R23") (pin "2") (pinfunction "2_2") (pintype "passive"))
      (node (ref "U10") (pin "4") (pinfunction "~{RE}_4") (pintype "bidirectional"))
    )
    (net (code "13") (name "/VBAT") (class "Default")
      (node (ref "U11") (pin "22") (pinfunction "VBAT_22") (pintype "power_in"))
    )
    (net (code "14") (name "/VIN") (class "Default")
      (node (ref "U11") (pin "1") (pinfunction "VIN_1") (pintype "power_in"))
    )
    (net (code "15") (name "/~{LDAC}") (class "Default")
      (node (ref "R29") (pin "2") (pinfunction "2_2") (pintype "passive"))
      (node (ref "R34") (pin "2") (pinfunction "2_2") (pintype "passive"))
      (node (ref "R35") (pin "2") (pinfunction "2_2") (pintype "passive"))
      (node (ref "U7") (pin "1") (pinfunction "~{LDAC}_1") (pintype "bidirectional"))
    )
    (net (code "16") (name "24V_IN") (class "Default")
      (node (ref "F2") (pin "1") (pinfunction "1_1") (pintype "passive"))
      (node (ref "J4") (pin "RED") (pinfunction "V+_RED") (pintype "power_in"))
    )
    (net (code "17") (name "485_5V") (class "Default")
      (node (ref "C26") (pin "1") (pinfunction "1_1") (pintype "passive"))
      (node (ref "J5") (pin "2") (pinfunction "2_2") (pintype "bidirectional"))
      (node (ref "J6") (pin "2") (pinfunction "2_2") (pintype "bidirectional"))
      (node (ref "U10") (pin "16") (pinfunction "VDD2_16") (pintype "bidirectional"))
    )
    (net (code "18") (name "485_A") (class "Default")
      (node (ref "J5") (pin "3") (pinfunction "3_3") (pintype "bidirectional"))
      (node (ref "J6") (pin "3") (pinfunction "3_3") (pintype "bidirectional"))
      (node (ref "U10") (pin "12") (pinfunction "A_12") (pintype "bidirectional"))
    )
    (net (code "19") (name "485_B") (class "Default")
      (node (ref "J5") (pin "4") (pinfunction "4_4") (pintype "bidirectional"))
      (node (ref "J6") (pin "4") (pinfunction "4_4") (pintype "bidirectional"))
      (node (ref "U10") (pin "13") (pinfunction "B_13") (pintype "bidirectional"))
    )
    (net (code "20") (name "485_GND") (class "Default")
      (node (ref "C26") (pin "2") (pinfunction "2_2") (pintype "passive"))
      (node (ref "J5") (pin "1") (pinfunction "1_1") (pintype "bidirectional"))
      (node (ref "J5") (pin "6") (pinfunction "6_6") (pintype "bidirectional"))
      (node (ref "J6") (pin "1") (pinfunction "1_1") (pintype "bidirectional"))
      (node (ref "J6") (pin "6") (pinfunction "6_6") (pintype "bidirectional"))
      (node (ref "U10") (pin "10") (pinfunction "GND2_10") (pintype "bidirectional"))
      (node (ref "U10") (pin "15") (pinfunction "GND2_15") (pintype "bidirectional"))
      (node (ref "U10") (pin "9") (pinfunction "GND2_9") (pintype "bidirectional"))
    )
    (net (code "21") (name "ADDR0") (class "Default")
      (node (ref "SJ_A16") (pin "2") (pinfunction "2_2") (pintype "passive"))
      (node (ref "SJ_A17") (pin "2") (pinfunction "2_2") (pintype "passive"))
      (node (ref "U7") (pin "2") (pinfunction "ADDR0_2") (pintype "bidirectional"))
    )
    (net (code "22") (name "CH1+") (class "Default")
      (node (ref "CH1+") (pin "1") (pinfunction "P_1") (pintype "passive"))
      (node (ref "U1") (pin "6") (pinfunction "+VOUT_6") (pintype "power_in"))
    )
    (net (code "23") (name "CH1-") (class "Default")
      (node (ref "C2") (pin "1") (pinfunction "1_1") (pintype "passive"))
      (node (ref "CH1-") (pin "1") (pinfunction "P_1") (pintype "passive"))
      (node (ref "U1") (pin "5") (pinfunction "-VOUT_5") (pintype "power_in"))
    )
    (net (code "24") (name "CH2+") (class "Default")
      (node (ref "CH2+") (pin "1") (pinfunction "P_1") (pintype "passive"))
      (node (ref "U2") (pin "6") (pinfunction "+VOUT_6") (pintype "power_in"))
    )
    (net (code "25") (name "CH2-") (class "Default")
      (node (ref "C5") (pin "1") (pinfunction "1_1") (pintype "passive"))
      (node (ref "CH2-") (pin "1") (pinfunction "P_1") (pintype "passive"))
      (node (ref "U2") (pin "5") (pinfunction "-VOUT_5") (pintype "power_in"))
    )
    (net (code "26") (name "CH3+") (class "Default")
      (node (ref "CH3+") (pin "1") (pinfunction "P_1") (pintype "passive"))
      (node (ref "U3") (pin "6") (pinfunction "+VOUT_6") (pintype "power_in"))
    )
    (net (code "27") (name "CH3-") (class "Default")
      (node (ref "C8") (pin "1") (pinfunction "1_1") (pintype "passive"))
      (node (ref "CH3-") (pin "1") (pinfunction "P_1") (pintype "passive"))
      (node (ref "U3") (pin "5") (pinfunction "-VOUT_5") (pintype "power_in"))
    )
    (net (code "28") (name "CH4+") (class "Default")
      (node (ref "CH4+") (pin "1") (pinfunction "P_1") (pintype "passive"))
      (node (ref "U4") (pin "6") (pinfunction "+VOUT_6") (pintype "power_in"))
    )
    (net (code "29") (name "CH4-") (class "Default")
      (node (ref "C11") (pin "1") (pinfunction "1_1") (pintype "passive"))
      (node (ref "CH4-") (pin "1") (pinfunction "P_1") (pintype "passive"))
      (node (ref "U4") (pin "5") (pinfunction "-VOUT_5") (pintype "power_in"))
    )
    (net (code "30") (name "CH5+") (class "Default")
      (node (ref "CH5+") (pin "1") (pinfunction "P_1") (pintype "passive"))
      (node (ref "U5") (pin "6") (pinfunction "+VOUT_6") (pintype "power_in"))
    )
    (net (code "31") (name "CH5-") (class "Default")
      (node (ref "C14") (pin "1") (pinfunction "1_1") (pintype "passive"))
      (node (ref "CH5-") (pin "1") (pinfunction "P_1") (pintype "passive"))
      (node (ref "U5") (pin "5") (pinfunction "-VOUT_5") (pintype "power_in"))
    )
    (net (code "32") (name "CH6+") (class "Default")
      (node (ref "CH6+") (pin "1") (pinfunction "P_1") (pintype "passive"))
      (node (ref "U6") (pin "6") (pinfunction "+VOUT_6") (pintype "power_in"))
    )
    (net (code "33") (name "CH6-") (class "Default")
      (node (ref "C17") (pin "1") (pinfunction "1_1") (pintype "passive"))
      (node (ref "CH6-") (pin "1") (pinfunction "P_1") (pintype "passive"))
      (node (ref "U6") (pin "5") (pinfunction "-VOUT_5") (pintype "power_in"))
    )
    (net (code "34") (name "DIM1") (class "Default")
      (node (ref "R6") (pin "2") (pinfunction "2_2") (pintype "passive"))
      (node (ref "U1") (pin "2") (pinfunction "ANALOGUE_DIM_2") (pintype "bidirectional"))
      (node (ref "U7") (pin "7") (pinfunction "VOUT_G_7") (pintype "bidirectional"))
    )
    (net (code "35") (name "DIM2") (class "Default")
      (node (ref "R7") (pin "2") (pinfunction "2_2") (pintype "passive"))
      (node (ref "U2") (pin "2") (pinfunction "ANALOGUE_DIM_2") (pintype "bidirectional"))
      (node (ref "U7") (pin "6") (pinfunction "VOUT_E_6") (pintype "bidirectional"))
    )
    (net (code "36") (name "DIM3") (class "Default")
      (node (ref "R8") (pin "2") (pinfunction "2_2") (pintype "passive"))
      (node (ref "U3") (pin "2") (pinfunction "ANALOGUE_DIM_2") (pintype "bidirectional"))
      (node (ref "U7") (pin "5") (pinfunction "VOUT_C_5") (pintype "bidirectional"))
    )
    (net (code "37") (name "DIM4") (class "Default")
      (node (ref "R9") (pin "2") (pinfunction "2_2") (pintype "passive"))
      (node (ref "U4") (pin "2") (pinfunction "ANALOGUE_DIM_2") (pintype "bidirectional"))
      (node (ref "U7") (pin "4") (pinfunction "VOUT_A_4") (pintype "bidirectional"))
    )
    (net (code "38") (name "DIM5") (class "Default")
      (node (ref "R14") (pin "2") (pinfunction "2_2") (pintype "passive"))
      (node (ref "U5") (pin "2") (pinfunction "ANALOGUE_DIM_2") (pintype "bidirectional"))
      (node (ref "U7") (pin "10") (pinfunction "VOUT_H_10") (pintype "bidirectional"))
    )
    (net (code "39") (name "DIM6") (class "Default")
      (node (ref "R26") (pin "2") (pinfunction "2_2") (pintype "passive"))
      (node (ref "U6") (pin "2") (pinfunction "ANALOGUE_DIM_2") (pintype "bidirectional"))
      (node (ref "U7") (pin "11") (pinfunction "VOUT_F_11") (pintype "bidirectional"))
    )
    (net (code "40") (name "GND") (class "Default")
      (node (ref "C1") (pin "2") (pinfunction "2_2") (pintype "passive"))
      (node (ref "C10") (pin "2") (pinfunction "2_2") (pintype "passive"))
      (node (ref "C11") (pin "2") (pinfunction "2_2") (pintype "passive"))
      (node (ref "C12") (pin "-") (pinfunction "2(-)_-") (pintype "passive"))
      (node (ref "C13") (pin "2") (pinfunction "2_2") (pintype "passive"))
      (node (ref "C14") (pin "2") (pinfunction "2_2") (pintype "passive"))
      (node (ref "C15") (pin "-") (pinfunction "2(-)_-") (pintype "passive"))
      (node (ref "C16") (pin "2") (pinfunction "2_2") (pintype "passive"))
      (node (ref "C17") (pin "2") (pinfunction "2_2") (pintype "passive"))
      (node (ref "C18") (pin "-") (pinfunction "2(-)_-") (pintype "passive"))
      (node (ref "C19") (pin "2") (pinfunction "2_2") (pintype "passive"))
      (node (ref "C2") (pin "2") (pinfunction "2_2") (pintype "passive"))
      (node (ref "C20") (pin "2") (pinfunction "2_2") (pintype "passive"))
      (node (ref "C21") (pin "2") (pinfunction "2_2") (pintype "passive"))
      (node (ref "C22") (pin "2") (pinfunction "2_2") (pintype "passive"))
      (node (ref "C23") (pin "2") (pinfunction "2_2") (pintype "passive"))
      (node (ref "C25") (pin "2") (pinfunction "2_2") (pintype "passive"))
      (node (ref "C27") (pin "2") (pinfunction "2_2") (pintype "passive"))
      (node (ref "C28") (pin "2") (pinfunction "2_2") (pintype "passive"))
      (node (ref "C29") (pin "2") (pinfunction "2_2") (pintype "passive"))
      (node (ref "C3") (pin "-") (pinfunction "2(-)_-") (pintype "passive"))
      (node (ref "C30") (pin "2") (pinfunction "2_2") (pintype "passive"))
      (node (ref "C31") (pin "2") (pinfunction "2_2") (pintype "passive"))
      (node (ref "C32") (pin "2") (pinfunction "2_2") (pintype "passive"))
      (node (ref "C33") (pin "2") (pinfunction "2_2") (pintype "passive"))
      (node (ref "C34") (pin "2") (pinfunction "2_2") (pintype "passive"))
      (node (ref "C36") (pin "2") (pinfunction "2_2") (pintype "passive"))
      (node (ref "C37") (pin "2") (pinfunction "2_2") (pintype "passive"))
      (node (ref "C38") (pin "2") (pinfunction "2_2") (pintype "passive"))
      (node (ref "C4") (pin "2") (pinfunction "2_2") (pintype "passive"))
      (node (ref "C5") (pin "2") (pinfunction "2_2") (pintype "passive"))
      (node (ref "C6") (pin "-") (pinfunction "2(-)_-") (pintype "passive"))
      (node (ref "C7") (pin "2") (pinfunction "2_2") (pintype "passive"))
      (node (ref "C8") (pin "2") (pinfunction "2_2") (pintype "passive"))
      (node (ref "C9") (pin "-") (pinfunction "2(-)_-") (pintype "passive"))
      (node (ref "CR2") (pin "2") (pinfunction "P$1_2") (pintype "bidirectional"))
      (node (ref "D1") (pin "C") (pinfunction "C_C") (pintype "passive"))
      (node (ref "D2") (pin "C") (pinfunction "C_C") (pintype "passive"))
      (node (ref "J1") (pin "4") (pinfunction "GND_4") (pintype "bidirectional"))
      (node (ref "J4") (pin "BLK") (pinfunction "GND_BLK") (pintype "power_in"))
      (node (ref "R29") (pin "1") (pinfunction "1_1") (pintype "passive"))
      (node (ref "R56") (pin "1") (pinfunction "1_1") (pintype "passive"))
      (node (ref "R57") (pin "1") (pinfunction "1_1") (pintype "passive"))
      (node (ref "R58") (pin "1") (pinfunction "1_1") (pintype "passive"))
      (node (ref "R59") (pin "1") (pinfunction "1_1") (pintype "passive"))
      (node (ref "R60") (pin "1") (pinfunction "1_1") (pintype "passive"))
      (node (ref "R61") (pin "1") (pinfunction "1_1") (pintype "passive"))
      (node (ref "R62") (pin "2") (pinfunction "2_2") (pintype "passive"))
      (node (ref "SJ_A12") (pin "1") (pinfunction "1_1") (pintype "passive"))
      (node (ref "SJ_A17") (pin "1") (pinfunction "1_1") (pintype "passive"))
      (node (ref "U1") (pin "4") (pinfunction "GND_4") (pintype "power_in"))
      (node (ref "U10") (pin "2") (pinfunction "GND1_2") (pintype "bidirectional"))
      (node (ref "U10") (pin "7") (pinfunction "GND1_7") (pintype "bidirectional"))
      (node (ref "U10") (pin "8") (pinfunction "GND1_8") (pintype "bidirectional"))
      (node (ref "U11") (pin "2") (pinfunction "GND_2") (pintype "power_in"))
      (node (ref "U11") (pin "21") (pinfunction "GND_21") (pintype "power_in"))
      (node (ref "U12") (pin "1") (pinfunction "GND_1") (pintype "power_in"))
      (node (ref "U13") (pin "2") (pinfunction "GND_2") (pintype "power_in"))
      (node (ref "U14") (pin "14") (pinfunction "GND_14") (pintype "power_in"))
      (node (ref "U14") (pin "25") (pinfunction "EXTCLK_25") (pintype "input"))
      (node (ref "U2") (pin "4") (pinfunction "GND_4") (pintype "power_in"))
      (node (ref "U3") (pin "4") (pinfunction "GND_4") (pintype "power_in"))
      (node (ref "U4") (pin "4") (pinfunction "GND_4") (pintype "power_in"))
      (node (ref "U5") (pin "4") (pinfunction "GND_4") (pintype "power_in"))
      (node (ref "U6") (pin "4") (pinfunction "GND_4") (pintype "power_in"))
      (node (ref "U7") (pin "14") (pinfunction "GND_14") (pintype "bidirectional"))
      (node (ref "U8") (pin "5") (pinfunction "GND2_5") (pintype "power_in"))
      (node (ref "U9") (pin "28") (pinfunction "VSS_28") (pintype "power_in"))
    )
    (net (code "41") (name "I2C_3V3") (class "Default")
      (node (ref "C24") (pin "1") (pinfunction "1_1") (pintype "passive"))
      (node (ref "J2") (pin "5") (pinfunction "5_5") (pintype "bidirectional"))
      (node (ref "J3") (pin "5") (pinfunction "5_5") (pintype "bidirectional"))
      (node (ref "J7") (pin "3V3") (pinfunction "3V3_3V3") (pintype "bidirectional"))
      (node (ref "R12") (pin "2") (pinfunction "2_2") (pintype "passive"))
      (node (ref "R13") (pin "2") (pinfunction "2_2") (pintype "passive"))
      (node (ref "SJ_A15") (pin "2") (pinfunction "2_2") (pintype "passive"))
      (node (ref "U8") (pin "1") (pinfunction "VCC1_1") (pintype "power_in"))
    )
    (net (code "42") (name "I2C_GND") (class "Default")
      (node (ref "C24") (pin "2") (pinfunction "2_2") (pintype "passive"))
      (node (ref "J2") (pin "1") (pinfunction "1_1") (pintype "bidirectional"))
      (node (ref "J3") (pin "1") (pinfunction "1_1") (pintype "bidirectional"))
      (node (ref "J7") (pin "GND") (pinfunction "GND_GND") (pintype "bidirectional"))
      (node (ref "SJ_A12") (pin "2") (pinfunction "2_2") (pintype "passive"))
      (node (ref "U8") (pin "4") (pinfunction "GND1_4") (pintype "power_in"))
    )
    (net (code "43") (name "I2C_IO") (class "Default")
      (node (ref "J2") (pin "2") (pinfunction "2_2") (pintype "bidirectional"))
      (node (ref "J3") (pin "2") (pinfunction "2_2") (pintype "bidirectional"))
    )
    (net (code "44") (name "Net-(D1-PadA)") (class "Default")
      (node (ref "D1") (pin "A") (pinfunction "A_A") (pintype "passive"))
      (node (ref "R27") (pin "1") (pinfunction "1_1") (pintype "passive"))
    )
    (net (code "45") (name "Net-(D2-PadA)") (class "Default")
      (node (ref "D2") (pin "A") (pinfunction "A_A") (pintype "passive"))
      (node (ref "R37") (pin "1") (pinfunction "1_1") (pintype "passive"))
    )
    (net (code "46") (name "Net-(U1-+VIN)") (class "Default")
      (node (ref "C1") (pin "1") (pinfunction "1_1") (pintype "passive"))
      (node (ref "L1") (pin "2") (pinfunction "2_2") (pintype "passive"))
      (node (ref "SJ_A6") (pin "1") (pinfunction "1_1") (pintype "passive"))
      (node (ref "U1") (pin "1") (pinfunction "+VIN_1") (pintype "power_in"))
    )
    (net (code "47") (name "Net-(U2-+VIN)") (class "Default")
      (node (ref "C4") (pin "1") (pinfunction "1_1") (pintype "passive"))
      (node (ref "L2") (pin "2") (pinfunction "2_2") (pintype "passive"))
      (node (ref "SJ_A7") (pin "1") (pinfunction "1_1") (pintype "passive"))
      (node (ref "U2") (pin "1") (pinfunction "+VIN_1") (pintype "power_in"))
    )
    (net (code "48") (name "Net-(U3-+VIN)") (class "Default")
      (node (ref "C7") (pin "1") (pinfunction "1_1") (pintype "passive"))
      (node (ref "L3") (pin "2") (pinfunction "2_2") (pintype "passive"))
      (node (ref "SJ_A8") (pin "1") (pinfunction "1_1") (pintype "passive"))
      (node (ref "U3") (pin "1") (pinfunction "+VIN_1") (pintype "power_in"))
    )
    (net (code "49") (name "Net-(U4-+VIN)") (class "Default")
      (node (ref "C10") (pin "1") (pinfunction "1_1") (pintype "passive"))
      (node (ref "L4") (pin "2") (pinfunction "2_2") (pintype "passive"))
      (node (ref "SJ_A9") (pin "1") (pinfunction "1_1") (pintype "passive"))
      (node (ref "U4") (pin "1") (pinfunction "+VIN_1") (pintype "power_in"))
    )
    (net (code "50") (name "Net-(U5-+VIN)") (class "Default")
      (node (ref "C13") (pin "1") (pinfunction "1_1") (pintype "passive"))
      (node (ref "L5") (pin "2") (pinfunction "2_2") (pintype "passive"))
      (node (ref "SJ_A10") (pin "1") (pinfunction "1_1") (pintype "passive"))
      (node (ref "U5") (pin "1") (pinfunction "+VIN_1") (pintype "power_in"))
    )
    (net (code "51") (name "Net-(U6-+VIN)") (class "Default")
      (node (ref "C16") (pin "1") (pinfunction "1_1") (pintype "passive"))
      (node (ref "L6") (pin "2") (pinfunction "2_2") (pintype "passive"))
      (node (ref "SJ_A11") (pin "1") (pinfunction "1_1") (pintype "passive"))
      (node (ref "U6") (pin "1") (pinfunction "+VIN_1") (pintype "power_in"))
    )
    (net (code "52") (name "Net-(U9-VCCD)") (class "Default")
      (node (ref "C33") (pin "1") (pinfunction "1_1") (pintype "passive"))
      (node (ref "U9") (pin "26") (pinfunction "VCCD_26") (pintype "power_in"))
    )
    (net (code "53") (name "Net-(U11-3V3)") (class "Default")
      (node (ref "C30") (pin "1") (pinfunction "1_1") (pintype "passive"))
      (node (ref "C34") (pin "1") (pinfunction "1_1") (pintype "passive"))
      (node (ref "R17") (pin "1") (pinfunction "1_1") (pintype "passive"))
      (node (ref "U11") (pin "24") (pinfunction "3V3_24") (pintype "power_in"))
    )
    (net (code "54") (name "Net-(U12-OUT)") (class "Default")
      (node (ref "C20") (pin "1") (pinfunction "1_1") (pintype "passive"))
      (node (ref "F1") (pin "1") (pinfunction "1_1") (pintype "passive"))
      (node (ref "U12") (pin "3") (pinfunction "OUT_3") (pintype "output"))
    )
    (net (code "55") (name "Net-(U13-OUT)") (class "Default")
      (node (ref "C23") (pin "1") (pinfunction "1_1") (pintype "passive"))
      (node (ref "F3") (pin "1") (pinfunction "1_1") (pintype "passive"))
      (node (ref "U13") (pin "3") (pinfunction "OUT_3") (pintype "power_in"))
    )
    (net (code "56") (name "P0[6]") (class "Default")
      (node (ref "R35") (pin "1") (pinfunction "1_1") (pintype "passive"))
      (node (ref "U9") (pin "23") (pinfunction "P0[6]_23") (pintype "bidirectional"))
    )
    (net (code "57") (name "P0[7]") (class "Default")
      (node (ref "R25") (pin "1") (pinfunction "1_1") (pintype "passive"))
      (node (ref "U9") (pin "24") (pinfunction "P0[7]_24") (pintype "bidirectional"))
    )
    (net (code "58") (name "P2[6]") (class "Default")
      (node (ref "R20") (pin "1") (pinfunction "1_1") (pintype "passive"))
      (node (ref "U9") (pin "9") (pinfunction "P2[6]_9") (pintype "bidirectional"))
    )
    (net (code "59") (name "P2[7]") (class "Default")
      (node (ref "R21") (pin "1") (pinfunction "1_1") (pintype "passive"))
      (node (ref "U9") (pin "10") (pinfunction "P2[7]_10") (pintype "bidirectional"))
    )
    (net (code "60") (name "PHOTON_A0") (class "Default")
      (node (ref "R24") (pin "1") (pinfunction "1_1") (pintype "passive"))
      (node (ref "U11") (pin "12") (pinfunction "A0_12") (pintype "bidirectional"))
    )
    (net (code "61") (name "PHOTON_A1") (class "Default")
      (node (ref "R34") (pin "1") (pinfunction "1_1") (pintype "passive"))
      (node (ref "U11") (pin "11") (pinfunction "A1_11") (pintype "bidirectional"))
    )
    (net (code "62") (name "PHOTON_D2") (class "Default")
      (node (ref "R22") (pin "1") (pinfunction "1_1") (pintype "passive"))
      (node (ref "U11") (pin "15") (pinfunction "D2_15") (pintype "bidirectional"))
    )
    (net (code "63") (name "PHOTON_D3") (class "Default")
      (node (ref "R23") (pin "1") (pinfunction "1_1") (pintype "passive"))
      (node (ref "U11") (pin "16") (pinfunction "D3_16") (pintype "bidirectional"))
    )
    (net (code "64") (name "PHOTON_D4") (class "Default")
      (node (ref "U11") (pin "17") (pinfunction "D4_17") (pintype "bidirectional"))
    )
    (net (code "65") (name "PHOTON_RX") (class "Default")
      (node (ref "R18") (pin "1") (pinfunction "1_1") (pintype "passive"))
      (node (ref "U11") (pin "4") (pinfunction "RX_4") (pintype "bidirectional"))
    )
    (net (code "66") (name "PHOTON_SCL") (class "Default")
      (node (ref "R5") (pin "1") (pinfunction "1_1") (pintype "passive"))
      (node (ref "U11") (pin "14") (pinfunction "D1_14") (pintype "bidirectional"))
    )
    (net (code "67") (name "PHOTON_SDA") (class "Default")
      (node (ref "R4") (pin "1") (pinfunction "1_1") (pintype "passive"))
      (node (ref "U11") (pin "13") (pinfunction "D0_13") (pintype "bidirectional"))
    )
    (net (code "68") (name "PHOTON_TX") (class "Default")
      (node (ref "R19") (pin "1") (pinfunction "1_1") (pintype "passive"))
      (node (ref "U11") (pin "3") (pinfunction "TX_3") (pintype "bidirectional"))
    )
    (net (code "69") (name "PWM1") (class "Default")
      (node (ref "U1") (pin "3") (pinfunction "PWM/ON/OFF_3") (pintype "bidirectional"))
      (node (ref "U14") (pin "12") (pinfunction "PWM6_12") (pintype "output"))
    )
    (net (code "70") (name "PWM2") (class "Default")
      (node (ref "U14") (pin "11") (pinfunction "PWM5_11") (pintype "output"))
      (node (ref "U2") (pin "3") (pinfunction "PWM/ON/OFF_3") (pintype "bidirectional"))
    )
    (net (code "71") (name "PWM3") (class "Default")
      (node (ref "U14") (pin "10") (pinfunction "PWM4_10") (pintype "output"))
      (node (ref "U3") (pin "3") (pinfunction "PWM/ON/OFF_3") (pintype "bidirectional"))
    )
    (net (code "72") (name "PWM4") (class "Default")
      (node (ref "U14") (pin "9") (pinfunction "PWM3_9") (pintype "output"))
      (node (ref "U4") (pin "3") (pinfunction "PWM/ON/OFF_3") (pintype "bidirectional"))
    )
    (net (code "73") (name "PWM5") (class "Default")
      (node (ref "U14") (pin "8") (pinfunction "PWM2_8") (pintype "output"))
      (node (ref "U5") (pin "3") (pinfunction "PWM/ON/OFF_3") (pintype "bidirectional"))
    )
    (net (code "74") (name "PWM6") (class "Default")
      (node (ref "U14") (pin "7") (pinfunction "PWM1_7") (pintype "output"))
      (node (ref "U6") (pin "3") (pinfunction "PWM/ON/OFF_3") (pintype "bidirectional"))
    )
    (net (code "75") (name "REG_3V3_150MA") (class "Default")
      (node (ref "F1") (pin "2") (pinfunction "2_2") (pintype "passive"))
      (node (ref "R36") (pin "1") (pinfunction "1_1") (pintype "passive"))
      (node (ref "R37") (pin "2") (pinfunction "2_2") (pintype "passive"))
    )
    (net (code "76") (name "REG_3V3_400MA") (class "Default")
      (node (ref "F3") (pin "2") (pinfunction "2_2") (pintype "passive"))
      (node (ref "R27") (pin "2") (pinfunction "2_2") (pintype "passive"))
      (node (ref "R38") (pin "1") (pinfunction "1_1") (pintype "passive"))
    )
    (net (code "77") (name "SCB0_I2C_SCL") (class "Default")
      (node (ref "R2") (pin "1") (pinfunction "1_1") (pintype "passive"))
      (node (ref "U9") (pin "15") (pinfunction "P4[0]_15") (pintype "bidirectional"))
    )
    (net (code "78") (name "SCB0_I2C_SDA") (class "Default")
      (node (ref "R1") (pin "1") (pinfunction "1_1") (pintype "passive"))
      (node (ref "U9") (pin "16") (pinfunction "P4[1]_16") (pintype "bidirectional"))
    )
    (net (code "79") (name "SCB1_RX[0]_SCL[0]") (class "Default")
      (node (ref "R15") (pin "1") (pinfunction "1_1") (pintype "passive"))
      (node (ref "R31") (pin "1") (pinfunction "1_1") (pintype "passive"))
      (node (ref "U9") (pin "11") (pinfunction "P3[0]_11") (pintype "bidirectional"))
    )
    (net (code "80") (name "SCB1_TX[0]_SDA[0]") (class "Default")
      (node (ref "R16") (pin "1") (pinfunction "1_1") (pintype "passive"))
      (node (ref "R30") (pin "1") (pinfunction "1_1") (pintype "passive"))
      (node (ref "U9") (pin "12") (pinfunction "P3[1]_12") (pintype "bidirectional"))
    )
    (net (code "81") (name "SCL") (class "Default")
      (node (ref "R2") (pin "2") (pinfunction "2_2") (pintype "passive"))
      (node (ref "R33") (pin "2") (pinfunction "2_2") (pintype "passive"))
      (node (ref "R5") (pin "2") (pinfunction "2_2") (pintype "passive"))
      (node (ref "SJ_A13") (pin "1") (pinfunction "1_1") (pintype "passive"))
      (node (ref "U14") (pin "26") (pinfunction "SCL_26") (pintype "bidirectional"))
      (node (ref "U7") (pin "16") (pinfunction "SCL_16") (pintype "bidirectional"))
    )
    (net (code "82") (name "SCL1") (class "Default")
      (node (ref "J2") (pin "3") (pinfunction "3_3") (pintype "bidirectional"))
      (node (ref "J3") (pin "3") (pinfunction "3_3") (pintype "bidirectional"))
      (node (ref "J7") (pin "SCL") (pinfunction "SCL_SCL") (pintype "bidirectional"))
      (node (ref "R12") (pin "1") (pinfunction "1_1") (pintype "passive"))
      (node (ref "SJ_A13") (pin "2") (pinfunction "2_2") (pintype "passive"))
      (node (ref "U8") (pin "3") (pinfunction "SCL1_3") (pintype "bidirectional"))
    )
    (net (code "83") (name "SCL2") (class "Default")
      (node (ref "R10") (pin "1") (pinfunction "1_1") (pintype "passive"))
      (node (ref "R31") (pin "2") (pinfunction "2_2") (pintype "passive"))
      (node (ref "R33") (pin "1") (pinfunction "1_1") (pintype "passive"))
      (node (ref "U8") (pin "6") (pinfunction "SCL2_6") (pintype "bidirectional"))
    )
    (net (code "84") (name "SDA") (class "Default")
      (node (ref "R1") (pin "2") (pinfunction "2_2") (pintype "passive"))
      (node (ref "R32") (pin "2") (pinfunction "2_2") (pintype "passive"))
      (node (ref "R4") (pin "2") (pinfunction "2_2") (pintype "passive"))
      (node (ref "SJ_A14") (pin "1") (pinfunction "1_1") (pintype "passive"))
      (node (ref "U14") (pin "27") (pinfunction "SDA_27") (pintype "bidirectional"))
      (node (ref "U7") (pin "15") (pinfunction "SDA_15") (pintype "bidirectional"))
    )
    (net (code "85") (name "SDA1") (class "Default")
      (node (ref "J2") (pin "4") (pinfunction "4_4") (pintype "bidirectional"))
      (node (ref "J3") (pin "4") (pinfunction "4_4") (pintype "bidirectional"))
      (node (ref "J7") (pin "SDA") (pinfunction "SDA_SDA") (pintype "bidirectional"))
      (node (ref "R13") (pin "1") (pinfunction "1_1") (pintype "passive"))
      (node (ref "SJ_A14") (pin "2") (pinfunction "2_2") (pintype "passive"))
      (node (ref "U8") (pin "2") (pinfunction "SDA1_2") (pintype "bidirectional"))
    )
    (net (code "86") (name "SDA2") (class "Default")
      (node (ref "R11") (pin "1") (pinfunction "1_1") (pintype "passive"))
      (node (ref "R30") (pin "2") (pinfunction "2_2") (pintype "passive"))
      (node (ref "R32") (pin "1") (pinfunction "1_1") (pintype "passive"))
      (node (ref "U8") (pin "7") (pinfunction "SDA2_7") (pintype "bidirectional"))
    )
    (net (code "87") (name "SWD_CLK[0]") (class "Default")
      (node (ref "J1") (pin "2") (pinfunction "SCLK_2") (pintype "bidirectional"))
      (node (ref "U9") (pin "14") (pinfunction "P3[3]_14") (pintype "bidirectional"))
    )
    (net (code "88") (name "SWD_IO[0]") (class "Default")
      (node (ref "J1") (pin "1") (pinfunction "SDAT_1") (pintype "bidirectional"))
      (node (ref "U9") (pin "13") (pinfunction "P3[2]_13") (pintype "bidirectional"))
    )
    (net (code "89") (name "UART_DE") (class "Default")
      (node (ref "R20") (pin "2") (pinfunction "2_2") (pintype "passive"))
      (node (ref "R22") (pin "2") (pinfunction "2_2") (pintype "passive"))
      (node (ref "U10") (pin "5") (pinfunction "DE_5") (pintype "bidirectional"))
    )
    (net (code "90") (name "UART_RX") (class "Default")
      (node (ref "R15") (pin "2") (pinfunction "2_2") (pintype "passive"))
      (node (ref "R18") (pin "2") (pinfunction "2_2") (pintype "passive"))
      (node (ref "U10") (pin "3") (pinfunction "RXD_3") (pintype "bidirectional"))
    )
    (net (code "91") (name "UART_TX") (class "Default")
      (node (ref "R16") (pin "2") (pinfunction "2_2") (pintype "passive"))
      (node (ref "R19") (pin "2") (pinfunction "2_2") (pintype "passive"))
      (node (ref "U10") (pin "6") (pinfunction "TXD_6") (pintype "bidirectional"))
    )
    (net (code "92") (name "VDDD") (class "Default")
      (node (ref "C31") (pin "1") (pinfunction "1_1") (pintype "passive"))
      (node (ref "C32") (pin "1") (pinfunction "1_1") (pintype "passive"))
      (node (ref "J1") (pin "5") (pinfunction "VTARG_5") (pintype "bidirectional"))
      (node (ref "R3") (pin "2") (pinfunction "2_2") (pintype "passive"))
      (node (ref "U9") (pin "27") (pinfunction "VDDD_27") (pintype "power_in"))
    )
    (net (code "93") (name "XRES") (class "Default")
      (node (ref "J1") (pin "3") (pinfunction "XRES_3") (pintype "bidirectional"))
      (node (ref "U9") (pin "25") (pinfunction "XRES_25") (pintype "input"))
    )
    (net (code "94") (name "unconnected-(J2-Pad6)") (class "Default")
      (node (ref "J2") (pin "6") (pinfunction "6_6") (pintype "bidirectional"))
    )
    (net (code "95") (name "unconnected-(J3-Pad6)") (class "Default")
      (node (ref "J3") (pin "6") (pinfunction "6_6") (pintype "bidirectional"))
    )
    (net (code "96") (name "unconnected-(J5-Pad5)") (class "Default")
      (node (ref "J5") (pin "5") (pinfunction "5_5") (pintype "bidirectional"))
    )
    (net (code "97") (name "unconnected-(J6-Pad5)") (class "Default")
      (node (ref "J6") (pin "5") (pinfunction "5_5") (pintype "bidirectional"))
    )
    (net (code "98") (name "unconnected-(U7-VOUT_B-Pad13)") (class "Default")
      (node (ref "U7") (pin "13") (pinfunction "VOUT_B_13") (pintype "bidirectional"))
    )
    (net (code "99") (name "unconnected-(U7-VOUT_D-Pad12)") (class "Default")
      (node (ref "U7") (pin "12") (pinfunction "VOUT_D_12") (pintype "bidirectional"))
    )
    (net (code "100") (name "unconnected-(U9-P0[0]-Pad19)") (class "Default")
      (node (ref "U9") (pin "19") (pinfunction "P0[0]_19") (pintype "bidirectional"))
    )
    (net (code "101") (name "unconnected-(U9-P0[1]-Pad20)") (class "Default")
      (node (ref "U9") (pin "20") (pinfunction "P0[1]_20") (pintype "bidirectional"))
    )
    (net (code "102") (name "unconnected-(U9-P0[2]-Pad21)") (class "Default")
      (node (ref "U9") (pin "21") (pinfunction "P0[2]_21") (pintype "bidirectional"))
    )
    (net (code "103") (name "unconnected-(U9-P0[3]-Pad22)") (class "Default")
      (node (ref "U9") (pin "22") (pinfunction "P0[3]_22") (pintype "bidirectional"))
    )
    (net (code "104") (name "unconnected-(U9-P1[0]-Pad1)") (class "Default")
      (node (ref "U9") (pin "1") (pinfunction "P1[0]_1") (pintype "bidirectional"))
    )
    (net (code "105") (name "unconnected-(U9-P1[1]-Pad2)") (class "Default")
      (node (ref "U9") (pin "2") (pinfunction "P1[1]_2") (pintype "bidirectional"))
    )
    (net (code "106") (name "unconnected-(U9-P1[2]-Pad3)") (class "Default")
      (node (ref "U9") (pin "3") (pinfunction "P1[2]_3") (pintype "bidirectional"))
    )
    (net (code "107") (name "unconnected-(U9-P1[7]-Pad4)") (class "Default")
      (node (ref "U9") (pin "4") (pinfunction "P1[7]_4") (pintype "bidirectional"))
    )
    (net (code "108") (name "unconnected-(U9-P2[2]-Pad5)") (class "Default")
      (node (ref "U9") (pin "5") (pinfunction "P2[2]_5") (pintype "bidirectional"))
    )
    (net (code "109") (name "unconnected-(U9-P2[3]-Pad6)") (class "Default")
      (node (ref "U9") (pin "6") (pinfunction "P2[3]_6") (pintype "bidirectional"))
    )
    (net (code "110") (name "unconnected-(U9-P2[4]-Pad7)") (class "Default")
      (node (ref "U9") (pin "7") (pinfunction "P2[4]_7") (pintype "bidirectional"))
    )
    (net (code "111") (name "unconnected-(U9-P2[5]-Pad8)") (class "Default")
      (node (ref "U9") (pin "8") (pinfunction "P2[5]_8") (pintype "bidirectional"))
    )
    (net (code "112") (name "unconnected-(U9-P4[2]-Pad17)") (class "Default")
      (node (ref "U9") (pin "17") (pinfunction "P4[2]_17") (pintype "bidirectional"))
    )
    (net (code "113") (name "unconnected-(U9-P4[3]-Pad18)") (class "Default")
      (node (ref "U9") (pin "18") (pinfunction "P4[3]_18") (pintype "bidirectional"))
    )
    (net (code "114") (name "unconnected-(U11-A2-Pad10)") (class "Default")
      (node (ref "U11") (pin "10") (pinfunction "A2_10") (pintype "bidirectional"))
    )
    (net (code "115") (name "unconnected-(U11-A3-Pad9)") (class "Default")
      (node (ref "U11") (pin "9") (pinfunction "A3_9") (pintype "bidirectional"))
    )
    (net (code "116") (name "unconnected-(U11-A4-Pad8)") (class "Default")
      (node (ref "U11") (pin "8") (pinfunction "A4_8") (pintype "bidirectional"))
    )
    (net (code "117") (name "unconnected-(U11-A5-Pad7)") (class "Default")
      (node (ref "U11") (pin "7") (pinfunction "A5_7") (pintype "bidirectional"))
    )
    (net (code "118") (name "unconnected-(U11-D5-Pad18)") (class "Default")
      (node (ref "U11") (pin "18") (pinfunction "D5_18") (pintype "bidirectional"))
    )
    (net (code "119") (name "unconnected-(U11-D6-Pad19)") (class "Default")
      (node (ref "U11") (pin "19") (pinfunction "D6_19") (pintype "bidirectional"))
    )
    (net (code "120") (name "unconnected-(U11-D7-Pad20)") (class "Default")
      (node (ref "U11") (pin "20") (pinfunction "D7_20") (pintype "bidirectional"))
    )
    (net (code "121") (name "unconnected-(U11-DAC-Pad6)") (class "Default")
      (node (ref "U11") (pin "6") (pinfunction "DAC_6") (pintype "bidirectional"))
    )
    (net (code "122") (name "unconnected-(U11-WKP-Pad5)") (class "Default")
      (node (ref "U11") (pin "5") (pinfunction "WKP_5") (pintype "bidirectional"))
    )
    (net (code "123") (name "unconnected-(U11-~{RST}-Pad23)") (class "Default")
      (node (ref "U11") (pin "23") (pinfunction "~{RST}_23") (pintype "bidirectional"))
    )
    (net (code "124") (name "unconnected-(U12-NC-Pad5)") (class "Default")
      (node (ref "U12") (pin "5") (pinfunction "NC_5") (pintype "passive"))
    )
    (net (code "125") (name "unconnected-(U12-NC_2-Pad4)") (class "Default")
      (node (ref "U12") (pin "4") (pinfunction "NC_2_4") (pintype "passive"))
    )
    (net (code "126") (name "unconnected-(U14-PWM0-Pad6)") (class "Default")
      (node (ref "U14") (pin "6") (pinfunction "PWM0_6") (pintype "output"))
    )
    (net (code "127") (name "unconnected-(U14-PWM7-Pad13)") (class "Default")
      (node (ref "U14") (pin "13") (pinfunction "PWM7_13") (pintype "output"))
    )
    (net (code "128") (name "unconnected-(U14-PWM8-Pad15)") (class "Default")
      (node (ref "U14") (pin "15") (pinfunction "PWM8_15") (pintype "output"))
    )
    (net (code "129") (name "unconnected-(U14-PWM9-Pad16)") (class "Default")
      (node (ref "U14") (pin "16") (pinfunction "PWM9_16") (pintype "output"))
    )
    (net (code "130") (name "unconnected-(U14-PWM10-Pad17)") (class "Default")
      (node (ref "U14") (pin "17") (pinfunction "PWM10_17") (pintype "output"))
    )
    (net (code "131") (name "unconnected-(U14-PWM11-Pad18)") (class "Default")
      (node (ref "U14") (pin "18") (pinfunction "PWM11_18") (pintype "output"))
    )
    (net (code "132") (name "unconnected-(U14-PWM12-Pad19)") (class "Default")
      (node (ref "U14") (pin "19") (pinfunction "PWM12_19") (pintype "output"))
    )
    (net (code "133") (name "unconnected-(U14-PWM13-Pad20)") (class "Default")
      (node (ref "U14") (pin "20") (pinfunction "PWM13_20") (pintype "output"))
    )
    (net (code "134") (name "unconnected-(U14-PWM14-Pad21)") (class "Default")
      (node (ref "U14") (pin "21") (pinfunction "PWM14_21") (pintype "output"))
    )
    (net (code "135") (name "unconnected-(U14-PWM15-Pad22)") (class "Default")
      (node (ref "U14") (pin "22") (pinfunction "PWM15_22") (pintype "output"))
    )
  )
)
